# guhPLC_V0_2.net
KiCad netlist of a schematic drawn in EAGLE
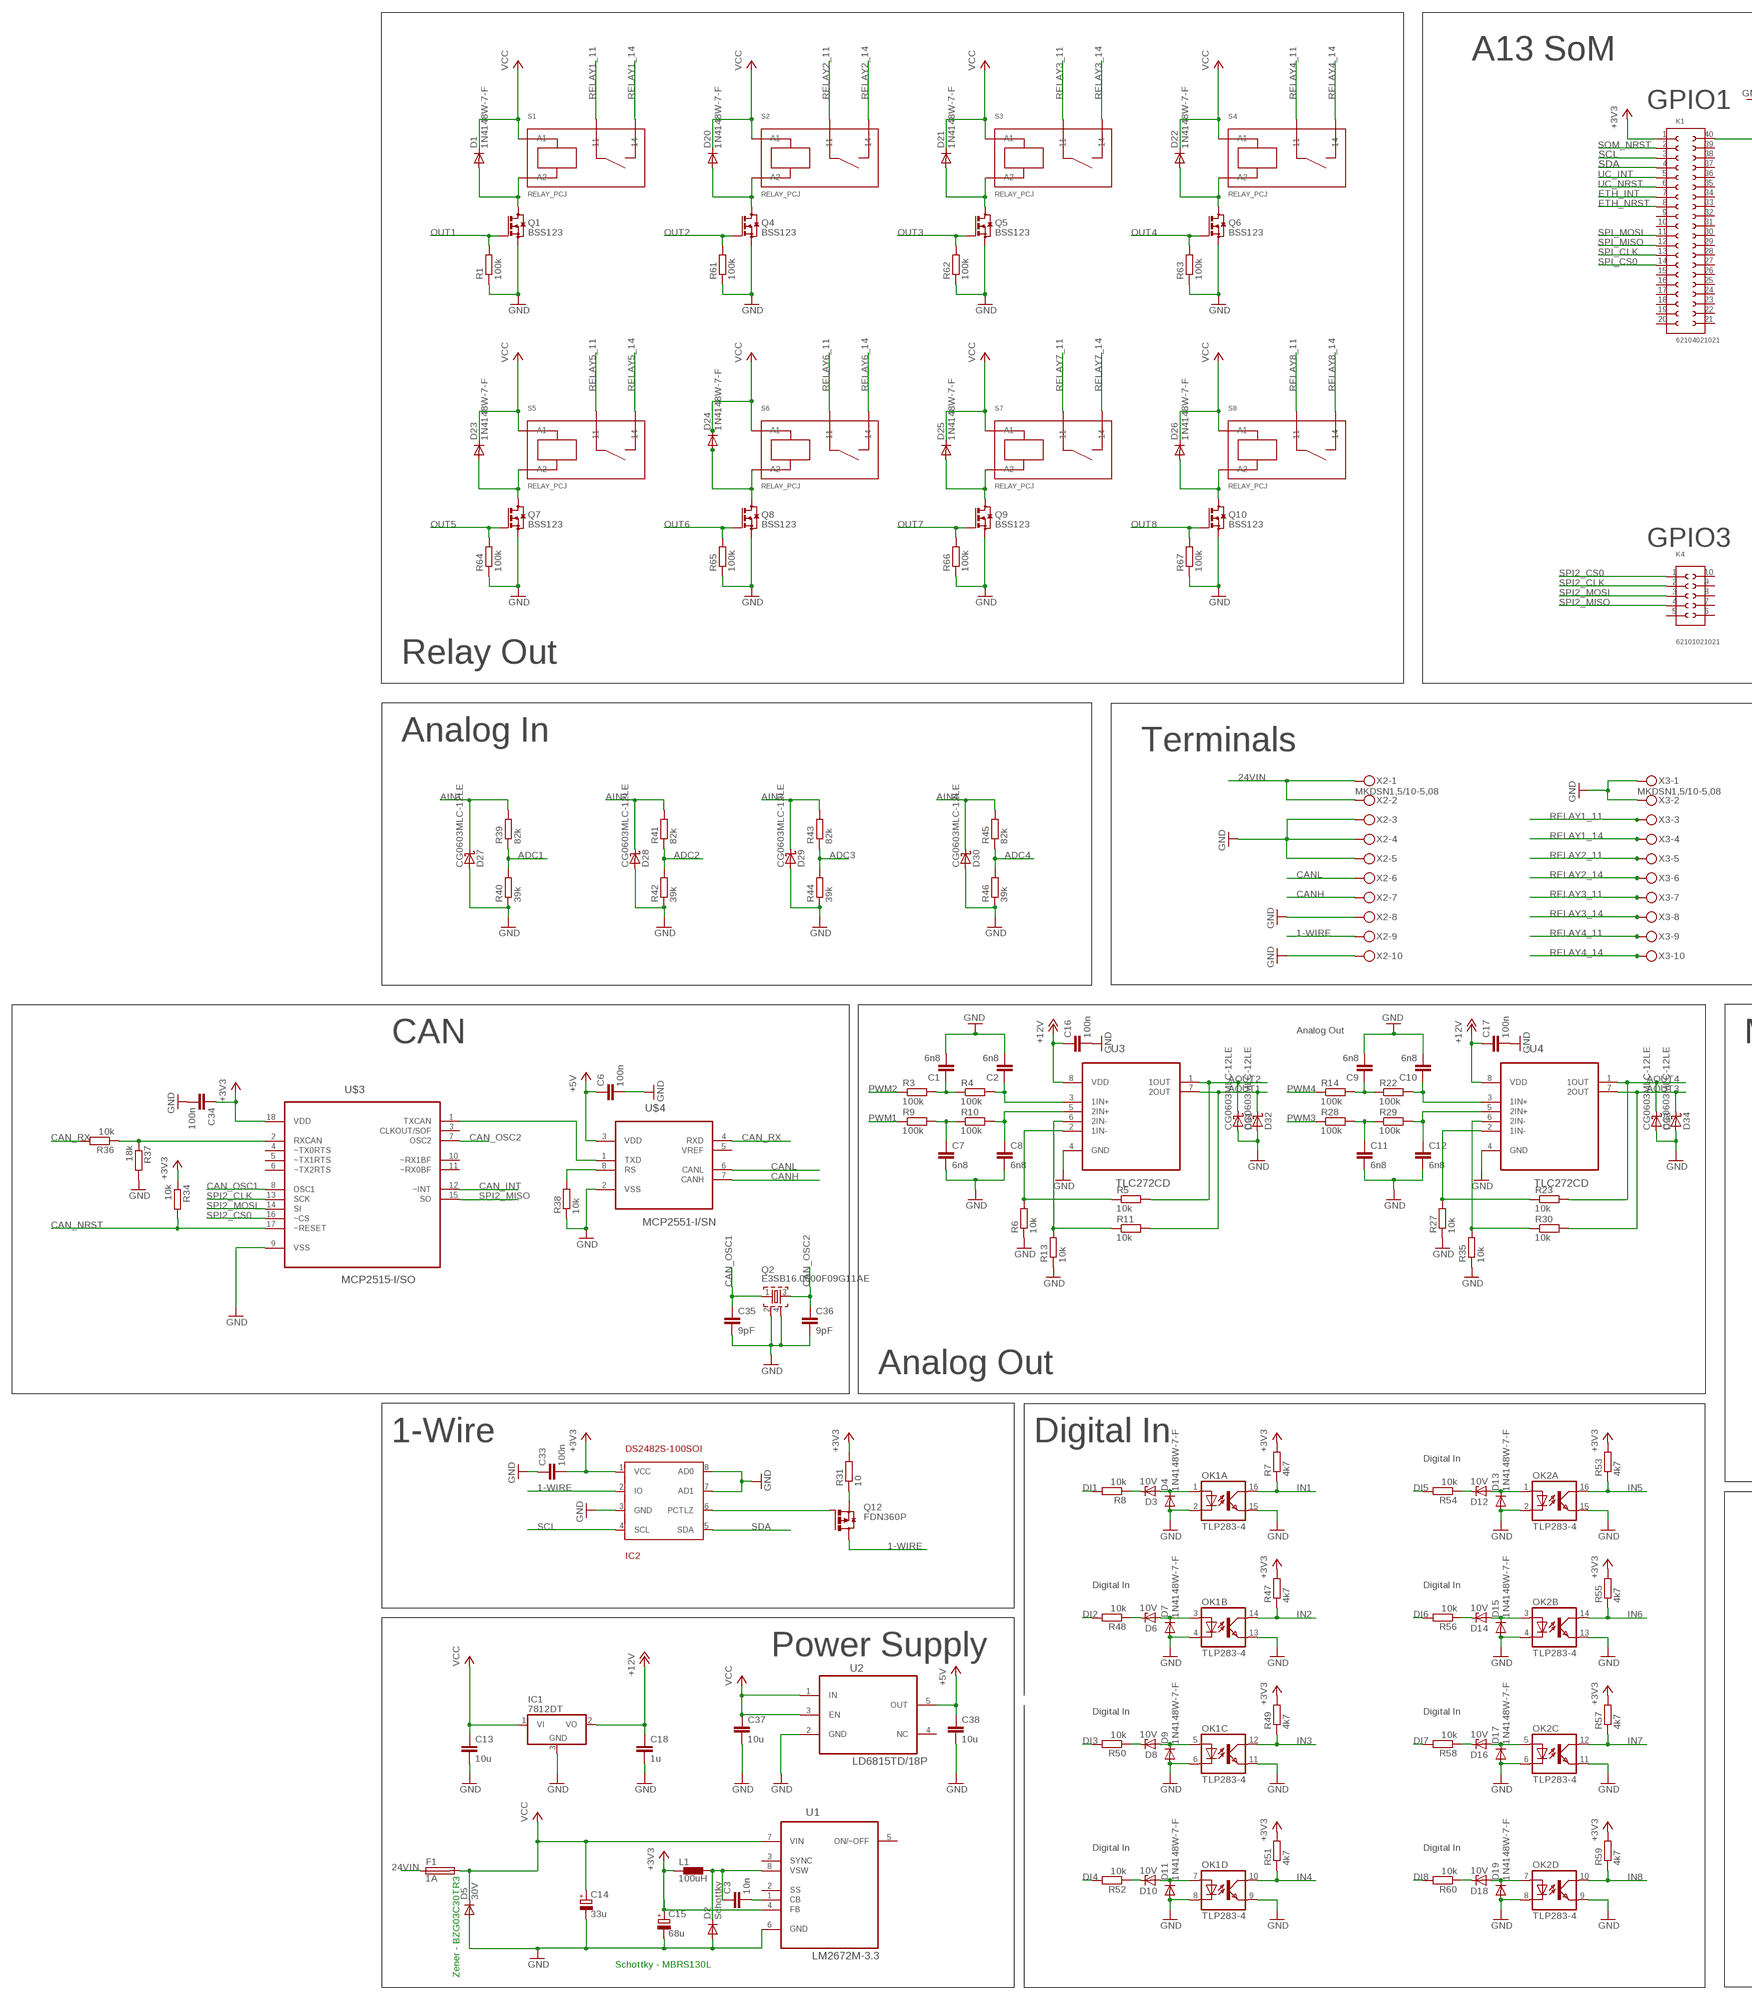
[diagram p0: schematic, sheet 1, part 1 of 2]
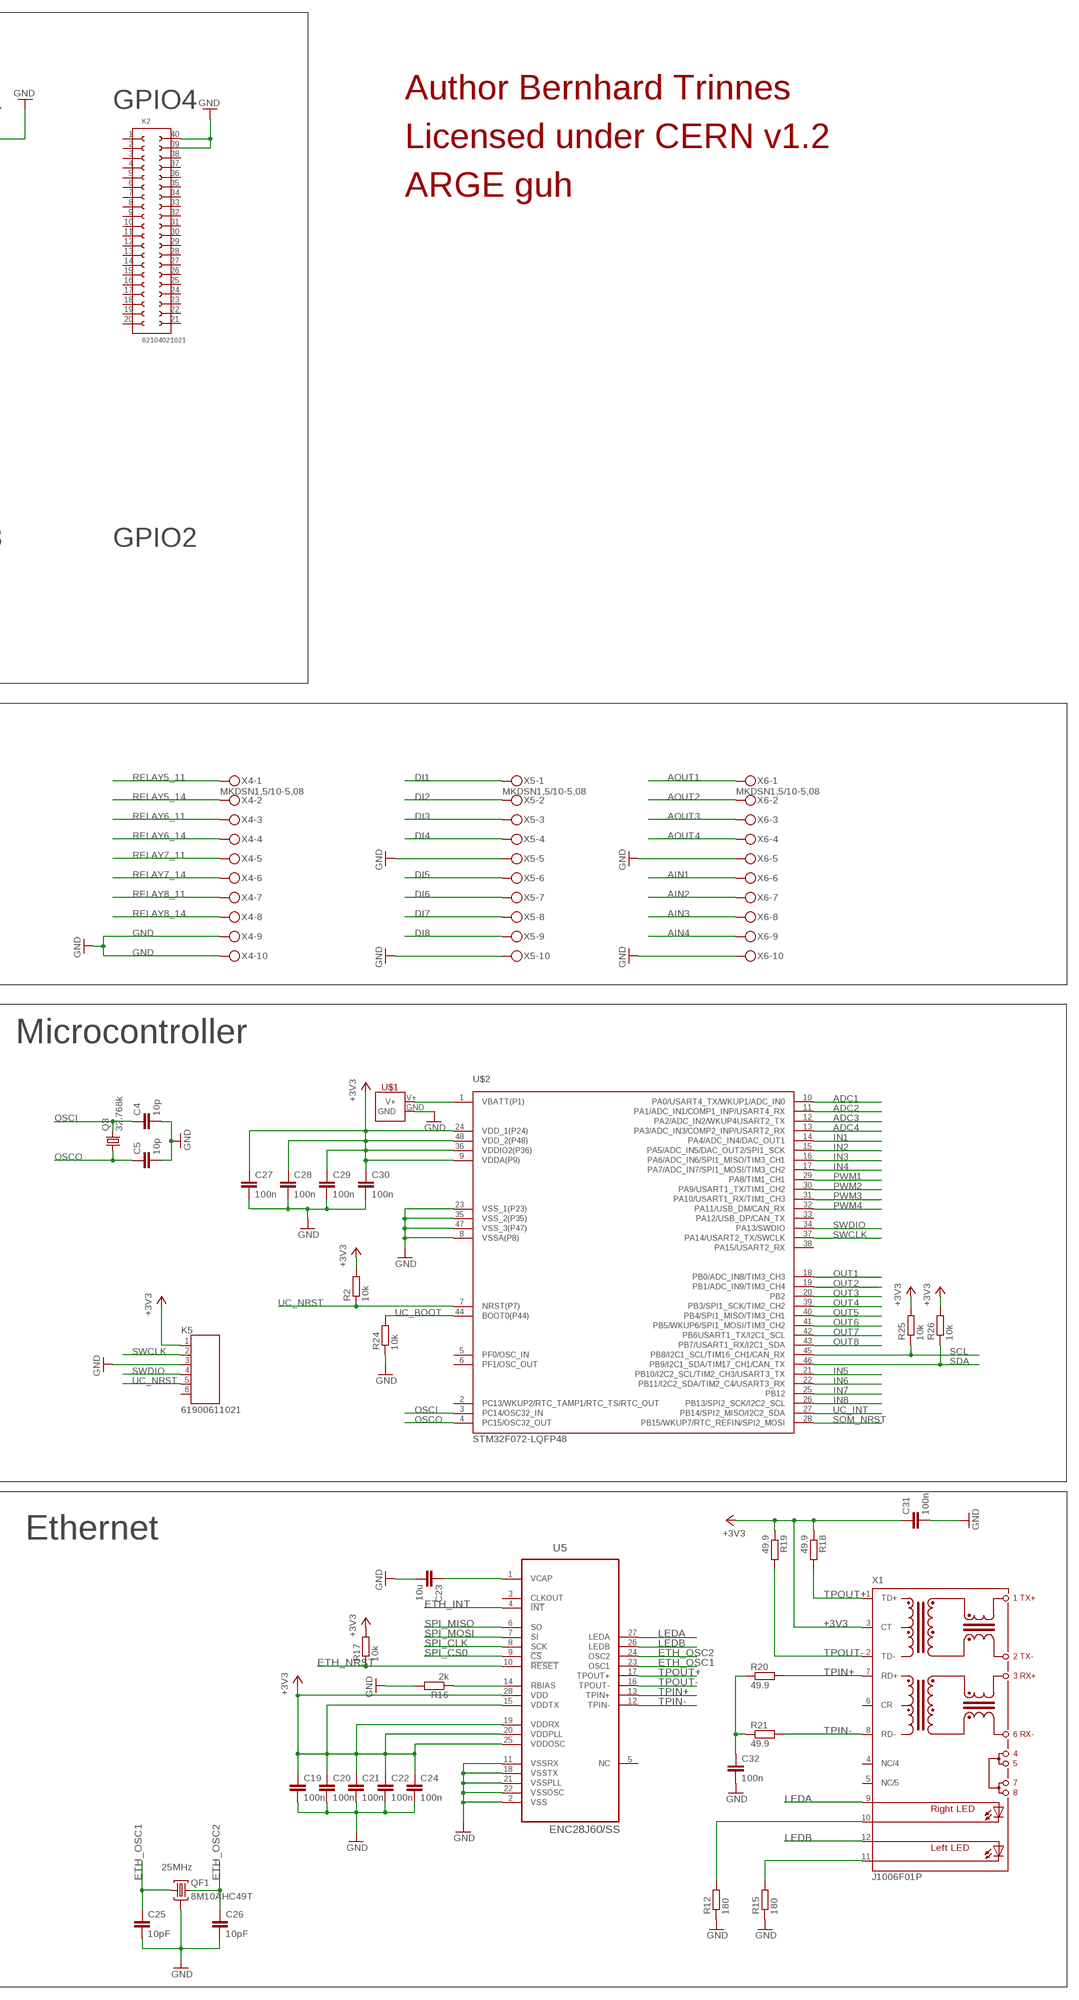
[diagram p1: schematic, sheet 1, part 2 of 2]

(export (version "E")
  (design (tool "Eeschema 10.0.6"))
  (components
    (comp (ref "C1")
      (value "6n8")
      (footprint "eagle-import:C0603")
      (libsource (lib "eagle-import") (part "C-EUC0603"))
    )
    (comp (ref "C2")
      (value "6n8")
      (footprint "eagle-import:C0603")
      (libsource (lib "eagle-import") (part "C-EUC0603"))
    )
    (comp (ref "C3")
      (value "10n")
      (footprint "eagle-import:C0603")
      (libsource (lib "eagle-import") (part "C-EUC0603"))
    )
    (comp (ref "C4")
      (value "10p")
      (footprint "eagle-import:C0603")
      (libsource (lib "eagle-import") (part "C-EUC0603"))
    )
    (comp (ref "C5")
      (value "10p")
      (footprint "eagle-import:C0603")
      (libsource (lib "eagle-import") (part "C-EUC0603"))
    )
    (comp (ref "C6")
      (value "100n")
      (footprint "eagle-import:C0603")
      (libsource (lib "eagle-import") (part "C-EUC0603"))
    )
    (comp (ref "C7")
      (value "6n8")
      (footprint "eagle-import:C0603")
      (libsource (lib "eagle-import") (part "C-EUC0603"))
    )
    (comp (ref "C8")
      (value "6n8")
      (footprint "eagle-import:C0603")
      (libsource (lib "eagle-import") (part "C-EUC0603"))
    )
    (comp (ref "C9")
      (value "6n8")
      (footprint "eagle-import:C0603")
      (libsource (lib "eagle-import") (part "C-EUC0603"))
    )
    (comp (ref "C10")
      (value "6n8")
      (footprint "eagle-import:C0603")
      (libsource (lib "eagle-import") (part "C-EUC0603"))
    )
    (comp (ref "C11")
      (value "6n8")
      (footprint "eagle-import:C0603")
      (libsource (lib "eagle-import") (part "C-EUC0603"))
    )
    (comp (ref "C12")
      (value "6n8")
      (footprint "eagle-import:C0603")
      (libsource (lib "eagle-import") (part "C-EUC0603"))
    )
    (comp (ref "C13")
      (value "10u")
      (footprint "eagle-import:C1206")
      (libsource (lib "eagle-import") (part "C-EUC1206"))
    )
    (comp (ref "C14")
      (value "33u")
      (footprint "eagle-import:CT7343")
      (libsource (lib "eagle-import") (part "CPOL-EUCT7343"))
    )
    (comp (ref "C15")
      (value "68u")
      (footprint "eagle-import:CT6032")
      (libsource (lib "eagle-import") (part "CPOL-EUCT6032"))
    )
    (comp (ref "C16")
      (value "100n")
      (footprint "eagle-import:C0603")
      (libsource (lib "eagle-import") (part "C-EUC0603"))
    )
    (comp (ref "C17")
      (value "100n")
      (footprint "eagle-import:C0603")
      (libsource (lib "eagle-import") (part "C-EUC0603"))
    )
    (comp (ref "C18")
      (value "1u")
      (footprint "eagle-import:C1206")
      (libsource (lib "eagle-import") (part "C-EUC1206"))
    )
    (comp (ref "C19")
      (value "100n")
      (footprint "eagle-import:C0603")
      (libsource (lib "eagle-import") (part "C-EUC0603"))
    )
    (comp (ref "C20")
      (value "100n")
      (footprint "eagle-import:C0603")
      (libsource (lib "eagle-import") (part "C-EUC0603"))
    )
    (comp (ref "C21")
      (value "100n")
      (footprint "eagle-import:C0603")
      (libsource (lib "eagle-import") (part "C-EUC0603"))
    )
    (comp (ref "C22")
      (value "100n")
      (footprint "eagle-import:C0603")
      (libsource (lib "eagle-import") (part "C-EUC0603"))
    )
    (comp (ref "C23")
      (value "10u")
      (footprint "eagle-import:C0603")
      (libsource (lib "eagle-import") (part "C-EUC0603"))
    )
    (comp (ref "C24")
      (value "100n")
      (footprint "eagle-import:C0603")
      (libsource (lib "eagle-import") (part "C-EUC0603"))
    )
    (comp (ref "C25")
      (value "10pF")
      (footprint "eagle-import:C0603")
      (libsource (lib "eagle-import") (part "C-EUC0603"))
    )
    (comp (ref "C26")
      (value "10pF")
      (footprint "eagle-import:C0603")
      (libsource (lib "eagle-import") (part "C-EUC0603"))
    )
    (comp (ref "C27")
      (value "100n")
      (footprint "eagle-import:C0603")
      (libsource (lib "eagle-import") (part "C-EUC0603"))
    )
    (comp (ref "C28")
      (value "100n")
      (footprint "eagle-import:C0603")
      (libsource (lib "eagle-import") (part "C-EUC0603"))
    )
    (comp (ref "C29")
      (value "100n")
      (footprint "eagle-import:C0603")
      (libsource (lib "eagle-import") (part "C-EUC0603"))
    )
    (comp (ref "C30")
      (value "100n")
      (footprint "eagle-import:C0603")
      (libsource (lib "eagle-import") (part "C-EUC0603"))
    )
    (comp (ref "C31")
      (value "100n")
      (footprint "eagle-import:C0603")
      (libsource (lib "eagle-import") (part "C-EUC0603"))
    )
    (comp (ref "C32")
      (value "100n")
      (footprint "eagle-import:C0402")
      (libsource (lib "eagle-import") (part "C-EUC0402"))
    )
    (comp (ref "C33")
      (value "100n")
      (footprint "eagle-import:C0603")
      (libsource (lib "eagle-import") (part "C-EUC0603"))
    )
    (comp (ref "C34")
      (value "100n")
      (footprint "eagle-import:C0603")
      (libsource (lib "eagle-import") (part "C-EUC0603"))
    )
    (comp (ref "C35")
      (value "9pF")
      (footprint "eagle-import:C0603")
      (libsource (lib "eagle-import") (part "C-EUC0603"))
    )
    (comp (ref "C36")
      (value "9pF")
      (footprint "eagle-import:C0603")
      (libsource (lib "eagle-import") (part "C-EUC0603"))
    )
    (comp (ref "C37")
      (value "10u")
      (footprint "eagle-import:C1206")
      (libsource (lib "eagle-import") (part "C-EUC1206"))
    )
    (comp (ref "C38")
      (value "10u")
      (footprint "eagle-import:C1206")
      (libsource (lib "eagle-import") (part "C-EUC1206"))
    )
    (comp (ref "D1")
      (value "1N4148W-7-F")
      (footprint "eagle-import:SOD123")
      (libsource (lib "eagle-import") (part "1N4148W-7-F"))
    )
    (comp (ref "D2")
      (value "Schottky")
      (footprint "eagle-import:DO214AA")
      (libsource (lib "eagle-import") (part "DIODE-DO214AA"))
    )
    (comp (ref "D3")
      (value "10V")
      (footprint "eagle-import:SOD80C")
      (libsource (lib "eagle-import") (part "ZENER-DIODESOD80C"))
    )
    (comp (ref "D4")
      (value "1N4148W-7-F")
      (footprint "eagle-import:SOD123")
      (libsource (lib "eagle-import") (part "1N4148W-7-F"))
    )
    (comp (ref "D5")
      (value "30V")
      (footprint "eagle-import:DO214AC")
      (libsource (lib "eagle-import") (part "DIODE-DO214AC"))
    )
    (comp (ref "D6")
      (value "10V")
      (footprint "eagle-import:SOD80C")
      (libsource (lib "eagle-import") (part "ZENER-DIODESOD80C"))
    )
    (comp (ref "D7")
      (value "1N4148W-7-F")
      (footprint "eagle-import:SOD123")
      (libsource (lib "eagle-import") (part "1N4148W-7-F"))
    )
    (comp (ref "D8")
      (value "10V")
      (footprint "eagle-import:SOD80C")
      (libsource (lib "eagle-import") (part "ZENER-DIODESOD80C"))
    )
    (comp (ref "D9")
      (value "1N4148W-7-F")
      (footprint "eagle-import:SOD123")
      (libsource (lib "eagle-import") (part "1N4148W-7-F"))
    )
    (comp (ref "D10")
      (value "10V")
      (footprint "eagle-import:SOD80C")
      (libsource (lib "eagle-import") (part "ZENER-DIODESOD80C"))
    )
    (comp (ref "D11")
      (value "1N4148W-7-F")
      (footprint "eagle-import:SOD123")
      (libsource (lib "eagle-import") (part "1N4148W-7-F"))
    )
    (comp (ref "D12")
      (value "10V")
      (footprint "eagle-import:SOD80C")
      (libsource (lib "eagle-import") (part "ZENER-DIODESOD80C"))
    )
    (comp (ref "D13")
      (value "1N4148W-7-F")
      (footprint "eagle-import:SOD123")
      (libsource (lib "eagle-import") (part "1N4148W-7-F"))
    )
    (comp (ref "D14")
      (value "10V")
      (footprint "eagle-import:SOD80C")
      (libsource (lib "eagle-import") (part "ZENER-DIODESOD80C"))
    )
    (comp (ref "D15")
      (value "1N4148W-7-F")
      (footprint "eagle-import:SOD123")
      (libsource (lib "eagle-import") (part "1N4148W-7-F"))
    )
    (comp (ref "D16")
      (value "10V")
      (footprint "eagle-import:SOD80C")
      (libsource (lib "eagle-import") (part "ZENER-DIODESOD80C"))
    )
    (comp (ref "D17")
      (value "1N4148W-7-F")
      (footprint "eagle-import:SOD123")
      (libsource (lib "eagle-import") (part "1N4148W-7-F"))
    )
    (comp (ref "D18")
      (value "10V")
      (footprint "eagle-import:SOD80C")
      (libsource (lib "eagle-import") (part "ZENER-DIODESOD80C"))
    )
    (comp (ref "D19")
      (value "1N4148W-7-F")
      (footprint "eagle-import:SOD123")
      (libsource (lib "eagle-import") (part "1N4148W-7-F"))
    )
    (comp (ref "D20")
      (value "1N4148W-7-F")
      (footprint "eagle-import:SOD123")
      (libsource (lib "eagle-import") (part "1N4148W-7-F"))
    )
    (comp (ref "D21")
      (value "1N4148W-7-F")
      (footprint "eagle-import:SOD123")
      (libsource (lib "eagle-import") (part "1N4148W-7-F"))
    )
    (comp (ref "D22")
      (value "1N4148W-7-F")
      (footprint "eagle-import:SOD123")
      (libsource (lib "eagle-import") (part "1N4148W-7-F"))
    )
    (comp (ref "D23")
      (value "1N4148W-7-F")
      (footprint "eagle-import:SOD123")
      (libsource (lib "eagle-import") (part "1N4148W-7-F"))
    )
    (comp (ref "D24")
      (value "1N4148W-7-F")
      (footprint "eagle-import:SOD123")
      (libsource (lib "eagle-import") (part "1N4148W-7-F"))
    )
    (comp (ref "D25")
      (value "1N4148W-7-F")
      (footprint "eagle-import:SOD123")
      (libsource (lib "eagle-import") (part "1N4148W-7-F"))
    )
    (comp (ref "D26")
      (value "1N4148W-7-F")
      (footprint "eagle-import:SOD123")
      (libsource (lib "eagle-import") (part "1N4148W-7-F"))
    )
    (comp (ref "D27")
      (value "CG0603MLC-12LE")
      (footprint "eagle-import:R0603")
      (libsource (lib "eagle-import") (part "CG0603MLC-12LE"))
    )
    (comp (ref "D28")
      (value "CG0603MLC-12LE")
      (footprint "eagle-import:R0603")
      (libsource (lib "eagle-import") (part "CG0603MLC-12LE"))
    )
    (comp (ref "D29")
      (value "CG0603MLC-12LE")
      (footprint "eagle-import:R0603")
      (libsource (lib "eagle-import") (part "CG0603MLC-12LE"))
    )
    (comp (ref "D30")
      (value "CG0603MLC-12LE")
      (footprint "eagle-import:R0603")
      (libsource (lib "eagle-import") (part "CG0603MLC-12LE"))
    )
    (comp (ref "D31")
      (value "CG0603MLC-12LE")
      (footprint "eagle-import:R0603")
      (libsource (lib "eagle-import") (part "CG0603MLC-12LE"))
    )
    (comp (ref "D32")
      (value "CG0603MLC-12LE")
      (footprint "eagle-import:R0603")
      (libsource (lib "eagle-import") (part "CG0603MLC-12LE"))
    )
    (comp (ref "D33")
      (value "CG0603MLC-12LE")
      (footprint "eagle-import:R0603")
      (libsource (lib "eagle-import") (part "CG0603MLC-12LE"))
    )
    (comp (ref "D34")
      (value "CG0603MLC-12LE")
      (footprint "eagle-import:R0603")
      (libsource (lib "eagle-import") (part "CG0603MLC-12LE"))
    )
    (comp (ref "F1")
      (value "1A")
      (footprint "eagle-import:LITTLEFUSE")
      (libsource (lib "eagle-import") (part "LITTLEFUSE"))
    )
    (comp (ref "IC1")
      (value "7812DT")
      (footprint "eagle-import:TO252")
      (libsource (lib "eagle-import") (part "78DT12"))
    )
    (comp (ref "IC2")
      (value "DS2482S-100SOI")
      (footprint "eagle-import:SOIC127P600X175-8N")
      (libsource (lib "eagle-import") (part "DS2482S-100SOI"))
    )
    (comp (ref "K1")
      (value "62104021021")
      (footprint "eagle-import:62104021021")
      (libsource (lib "eagle-import") (part "62104021021"))
    )
    (comp (ref "K2")
      (value "62104021021")
      (footprint "eagle-import:62104021021")
      (libsource (lib "eagle-import") (part "62104021021"))
    )
    (comp (ref "K4")
      (value "62101021021")
      (footprint "eagle-import:62101021021")
      (libsource (lib "eagle-import") (part "62101021021"))
    )
    (comp (ref "K5")
      (value "61900611021")
      (footprint "eagle-import:61900611021")
      (libsource (lib "eagle-import") (part "61900611021"))
    )
    (comp (ref "L1")
      (value "100uH")
      (footprint "eagle-import:DR1030")
      (libsource (lib "eagle-import") (part "DR1030"))
    )
    (comp (ref "OK1")
      (value "TLP283-4")
      (footprint "eagle-import:MINI-FLAT-16")
      (libsource (lib "eagle-import") (part "TLP283-4"))
    )
    (comp (ref "OK2")
      (value "TLP283-4")
      (footprint "eagle-import:MINI-FLAT-16")
      (libsource (lib "eagle-import") (part "TLP283-4"))
    )
    (comp (ref "Q1")
      (value "BSS123")
      (footprint "eagle-import:SOT23")
      (libsource (lib "eagle-import") (part "BSS123"))
    )
    (comp (ref "Q2")
      (value "E3SB16.0000F09G11AE")
      (footprint "eagle-import:E3SBXXXXXXXF09G11AE")
      (libsource (lib "eagle-import") (part "E3SB16.0000F09G11AE"))
    )
    (comp (ref "Q3")
      (value "32.768k")
      (footprint "eagle-import:TC26H")
      (libsource (lib "eagle-import") (part "CRYSTALTC26H"))
    )
    (comp (ref "Q4")
      (value "BSS123")
      (footprint "eagle-import:SOT23")
      (libsource (lib "eagle-import") (part "BSS123"))
    )
    (comp (ref "Q5")
      (value "BSS123")
      (footprint "eagle-import:SOT23")
      (libsource (lib "eagle-import") (part "BSS123"))
    )
    (comp (ref "Q6")
      (value "BSS123")
      (footprint "eagle-import:SOT23")
      (libsource (lib "eagle-import") (part "BSS123"))
    )
    (comp (ref "Q7")
      (value "BSS123")
      (footprint "eagle-import:SOT23")
      (libsource (lib "eagle-import") (part "BSS123"))
    )
    (comp (ref "Q8")
      (value "BSS123")
      (footprint "eagle-import:SOT23")
      (libsource (lib "eagle-import") (part "BSS123"))
    )
    (comp (ref "Q9")
      (value "BSS123")
      (footprint "eagle-import:SOT23")
      (libsource (lib "eagle-import") (part "BSS123"))
    )
    (comp (ref "Q10")
      (value "BSS123")
      (footprint "eagle-import:SOT23")
      (libsource (lib "eagle-import") (part "BSS123"))
    )
    (comp (ref "Q12")
      (value "FDN360P")
      (footprint "eagle-import:SUPER-SOT3")
      (libsource (lib "eagle-import") (part "FDN360P"))
    )
    (comp (ref "QF1")
      (value "8M10AHC49T")
      (footprint "eagle-import:HC49U")
      (libsource (lib "eagle-import") (part "8M10AHC49T"))
    )
    (comp (ref "R1")
      (value "100k")
      (footprint "eagle-import:R0603")
      (libsource (lib "eagle-import") (part "R-EU_R0603"))
    )
    (comp (ref "R2")
      (value "10k")
      (footprint "eagle-import:R0603")
      (libsource (lib "eagle-import") (part "R-EU_R0603"))
    )
    (comp (ref "R3")
      (value "100k")
      (footprint "eagle-import:R0603")
      (libsource (lib "eagle-import") (part "R-EU_R0603"))
    )
    (comp (ref "R4")
      (value "100k")
      (footprint "eagle-import:R0603")
      (libsource (lib "eagle-import") (part "R-EU_R0603"))
    )
    (comp (ref "R5")
      (value "10k")
      (footprint "eagle-import:R0805")
      (libsource (lib "eagle-import") (part "R-EU_R0805"))
    )
    (comp (ref "R6")
      (value "10k")
      (footprint "eagle-import:R0805")
      (libsource (lib "eagle-import") (part "R-EU_R0805"))
    )
    (comp (ref "R7")
      (value "4k7")
      (footprint "eagle-import:R0603")
      (libsource (lib "eagle-import") (part "R-EU_R0603"))
    )
    (comp (ref "R8")
      (value "10k")
      (footprint "eagle-import:R0805")
      (libsource (lib "eagle-import") (part "R-EU_R0805"))
    )
    (comp (ref "R9")
      (value "100k")
      (footprint "eagle-import:R0603")
      (libsource (lib "eagle-import") (part "R-EU_R0603"))
    )
    (comp (ref "R10")
      (value "100k")
      (footprint "eagle-import:R0603")
      (libsource (lib "eagle-import") (part "R-EU_R0603"))
    )
    (comp (ref "R11")
      (value "10k")
      (footprint "eagle-import:R0805")
      (libsource (lib "eagle-import") (part "R-EU_R0805"))
    )
    (comp (ref "R12")
      (value "180")
      (footprint "eagle-import:R0603")
      (libsource (lib "eagle-import") (part "R-EU_R0603"))
    )
    (comp (ref "R13")
      (value "10k")
      (footprint "eagle-import:R0805")
      (libsource (lib "eagle-import") (part "R-EU_R0805"))
    )
    (comp (ref "R14")
      (value "100k")
      (footprint "eagle-import:R0603")
      (libsource (lib "eagle-import") (part "R-EU_R0603"))
    )
    (comp (ref "R15")
      (value "180")
      (footprint "eagle-import:R0603")
      (libsource (lib "eagle-import") (part "R-EU_R0603"))
    )
    (comp (ref "R16")
      (value "2k")
      (footprint "eagle-import:R0603")
      (libsource (lib "eagle-import") (part "R-EU_R0603"))
    )
    (comp (ref "R17")
      (value "10k")
      (footprint "eagle-import:R0603")
      (libsource (lib "eagle-import") (part "R-EU_R0603"))
    )
    (comp (ref "R18")
      (value "49.9")
      (footprint "eagle-import:R0603")
      (libsource (lib "eagle-import") (part "R-EU_R0603"))
    )
    (comp (ref "R19")
      (value "49.9")
      (footprint "eagle-import:R0603")
      (libsource (lib "eagle-import") (part "R-EU_R0603"))
    )
    (comp (ref "R20")
      (value "49.9")
      (footprint "eagle-import:R0603")
      (libsource (lib "eagle-import") (part "R-EU_R0603"))
    )
    (comp (ref "R21")
      (value "49.9")
      (footprint "eagle-import:R0603")
      (libsource (lib "eagle-import") (part "R-EU_R0603"))
    )
    (comp (ref "R22")
      (value "100k")
      (footprint "eagle-import:R0603")
      (libsource (lib "eagle-import") (part "R-EU_R0603"))
    )
    (comp (ref "R23")
      (value "10k")
      (footprint "eagle-import:R0805")
      (libsource (lib "eagle-import") (part "R-EU_R0805"))
    )
    (comp (ref "R24")
      (value "10k")
      (footprint "eagle-import:R0603")
      (libsource (lib "eagle-import") (part "R-EU_R0603"))
    )
    (comp (ref "R25")
      (value "10k")
      (footprint "eagle-import:R0603")
      (libsource (lib "eagle-import") (part "R-EU_R0603"))
    )
    (comp (ref "R26")
      (value "10k")
      (footprint "eagle-import:R0603")
      (libsource (lib "eagle-import") (part "R-EU_R0603"))
    )
    (comp (ref "R27")
      (value "10k")
      (footprint "eagle-import:R0805")
      (libsource (lib "eagle-import") (part "R-EU_R0805"))
    )
    (comp (ref "R28")
      (value "100k")
      (footprint "eagle-import:R0603")
      (libsource (lib "eagle-import") (part "R-EU_R0603"))
    )
    (comp (ref "R29")
      (value "100k")
      (footprint "eagle-import:R0603")
      (libsource (lib "eagle-import") (part "R-EU_R0603"))
    )
    (comp (ref "R30")
      (value "10k")
      (footprint "eagle-import:R0805")
      (libsource (lib "eagle-import") (part "R-EU_R0805"))
    )
    (comp (ref "R31")
      (value "10")
      (footprint "eagle-import:R0805")
      (libsource (lib "eagle-import") (part "R-EU_R0805"))
    )
    (comp (ref "R34")
      (value "10k")
      (footprint "eagle-import:R0603")
      (libsource (lib "eagle-import") (part "R-EU_R0603"))
    )
    (comp (ref "R35")
      (value "10k")
      (footprint "eagle-import:R0805")
      (libsource (lib "eagle-import") (part "R-EU_R0805"))
    )
    (comp (ref "R36")
      (value "10k")
      (footprint "eagle-import:R0603")
      (libsource (lib "eagle-import") (part "R-EU_R0603"))
    )
    (comp (ref "R37")
      (value "18k")
      (footprint "eagle-import:R0603")
      (libsource (lib "eagle-import") (part "R-EU_R0603"))
    )
    (comp (ref "R38")
      (value "10k")
      (footprint "eagle-import:R0603")
      (libsource (lib "eagle-import") (part "R-EU_R0603"))
    )
    (comp (ref "R39")
      (value "82k")
      (footprint "eagle-import:R0805")
      (libsource (lib "eagle-import") (part "R-EU_R0805"))
    )
    (comp (ref "R40")
      (value "39k")
      (footprint "eagle-import:R0805")
      (libsource (lib "eagle-import") (part "R-EU_R0805"))
    )
    (comp (ref "R41")
      (value "82k")
      (footprint "eagle-import:R0805")
      (libsource (lib "eagle-import") (part "R-EU_R0805"))
    )
    (comp (ref "R42")
      (value "39k")
      (footprint "eagle-import:R0805")
      (libsource (lib "eagle-import") (part "R-EU_R0805"))
    )
    (comp (ref "R43")
      (value "82k")
      (footprint "eagle-import:R0805")
      (libsource (lib "eagle-import") (part "R-EU_R0805"))
    )
    (comp (ref "R44")
      (value "39k")
      (footprint "eagle-import:R0805")
      (libsource (lib "eagle-import") (part "R-EU_R0805"))
    )
    (comp (ref "R45")
      (value "82k")
      (footprint "eagle-import:R0805")
      (libsource (lib "eagle-import") (part "R-EU_R0805"))
    )
    (comp (ref "R46")
      (value "39k")
      (footprint "eagle-import:R0805")
      (libsource (lib "eagle-import") (part "R-EU_R0805"))
    )
    (comp (ref "R47")
      (value "4k7")
      (footprint "eagle-import:R0603")
      (libsource (lib "eagle-import") (part "R-EU_R0603"))
    )
    (comp (ref "R48")
      (value "10k")
      (footprint "eagle-import:R0805")
      (libsource (lib "eagle-import") (part "R-EU_R0805"))
    )
    (comp (ref "R49")
      (value "4k7")
      (footprint "eagle-import:R0603")
      (libsource (lib "eagle-import") (part "R-EU_R0603"))
    )
    (comp (ref "R50")
      (value "10k")
      (footprint "eagle-import:R0805")
      (libsource (lib "eagle-import") (part "R-EU_R0805"))
    )
    (comp (ref "R51")
      (value "4k7")
      (footprint "eagle-import:R0603")
      (libsource (lib "eagle-import") (part "R-EU_R0603"))
    )
    (comp (ref "R52")
      (value "10k")
      (footprint "eagle-import:R0805")
      (libsource (lib "eagle-import") (part "R-EU_R0805"))
    )
    (comp (ref "R53")
      (value "4k7")
      (footprint "eagle-import:R0603")
      (libsource (lib "eagle-import") (part "R-EU_R0603"))
    )
    (comp (ref "R54")
      (value "10k")
      (footprint "eagle-import:R0805")
      (libsource (lib "eagle-import") (part "R-EU_R0805"))
    )
    (comp (ref "R55")
      (value "4k7")
      (footprint "eagle-import:R0603")
      (libsource (lib "eagle-import") (part "R-EU_R0603"))
    )
    (comp (ref "R56")
      (value "10k")
      (footprint "eagle-import:R0805")
      (libsource (lib "eagle-import") (part "R-EU_R0805"))
    )
    (comp (ref "R57")
      (value "4k7")
      (footprint "eagle-import:R0603")
      (libsource (lib "eagle-import") (part "R-EU_R0603"))
    )
    (comp (ref "R58")
      (value "10k")
      (footprint "eagle-import:R0805")
      (libsource (lib "eagle-import") (part "R-EU_R0805"))
    )
    (comp (ref "R59")
      (value "4k7")
      (footprint "eagle-import:R0603")
      (libsource (lib "eagle-import") (part "R-EU_R0603"))
    )
    (comp (ref "R60")
      (value "10k")
      (footprint "eagle-import:R0805")
      (libsource (lib "eagle-import") (part "R-EU_R0805"))
    )
    (comp (ref "R61")
      (value "100k")
      (footprint "eagle-import:R0603")
      (libsource (lib "eagle-import") (part "R-EU_R0603"))
    )
    (comp (ref "R62")
      (value "100k")
      (footprint "eagle-import:R0603")
      (libsource (lib "eagle-import") (part "R-EU_R0603"))
    )
    (comp (ref "R63")
      (value "100k")
      (footprint "eagle-import:R0603")
      (libsource (lib "eagle-import") (part "R-EU_R0603"))
    )
    (comp (ref "R64")
      (value "100k")
      (footprint "eagle-import:R0603")
      (libsource (lib "eagle-import") (part "R-EU_R0603"))
    )
    (comp (ref "R65")
      (value "100k")
      (footprint "eagle-import:R0603")
      (libsource (lib "eagle-import") (part "R-EU_R0603"))
    )
    (comp (ref "R66")
      (value "100k")
      (footprint "eagle-import:R0603")
      (libsource (lib "eagle-import") (part "R-EU_R0603"))
    )
    (comp (ref "R67")
      (value "100k")
      (footprint "eagle-import:R0603")
      (libsource (lib "eagle-import") (part "R-EU_R0603"))
    )
    (comp (ref "S1")
      (value "RELAY_PCJ")
      (footprint "eagle-import:RELAY_PCJ")
      (libsource (lib "eagle-import") (part "RELAY_PCJ"))
    )
    (comp (ref "S2")
      (value "RELAY_PCJ")
      (footprint "eagle-import:RELAY_PCJ")
      (libsource (lib "eagle-import") (part "RELAY_PCJ"))
    )
    (comp (ref "S3")
      (value "RELAY_PCJ")
      (footprint "eagle-import:RELAY_PCJ")
      (libsource (lib "eagle-import") (part "RELAY_PCJ"))
    )
    (comp (ref "S4")
      (value "RELAY_PCJ")
      (footprint "eagle-import:RELAY_PCJ")
      (libsource (lib "eagle-import") (part "RELAY_PCJ"))
    )
    (comp (ref "S5")
      (value "RELAY_PCJ")
      (footprint "eagle-import:RELAY_PCJ")
      (libsource (lib "eagle-import") (part "RELAY_PCJ"))
    )
    (comp (ref "S6")
      (value "RELAY_PCJ")
      (footprint "eagle-import:RELAY_PCJ")
      (libsource (lib "eagle-import") (part "RELAY_PCJ"))
    )
    (comp (ref "S7")
      (value "RELAY_PCJ")
      (footprint "eagle-import:RELAY_PCJ")
      (libsource (lib "eagle-import") (part "RELAY_PCJ"))
    )
    (comp (ref "S8")
      (value "RELAY_PCJ")
      (footprint "eagle-import:RELAY_PCJ")
      (libsource (lib "eagle-import") (part "RELAY_PCJ"))
    )
    (comp (ref "U$1")
      (value "MULTICOMP-CH7410-2032LF")
      (footprint "eagle-import:MULTICOMP-CH7410-2032LF")
      (libsource (lib "eagle-import") (part "MULTICOMP-CH7410-2032LF"))
    )
    (comp (ref "U$2")
      (value "STM32F072-LQFP48")
      (footprint "eagle-import:LQFP48")
      (libsource (lib "eagle-import") (part "STM32F072-LQFP48"))
    )
    (comp (ref "U$3")
      (value "MCP2515-I/SO")
      (footprint "eagle-import:SOIC127P1034X264-18N")
      (libsource (lib "eagle-import") (part "MCP2515-I/SO"))
    )
    (comp (ref "U$4")
      (value "MCP2551-I/SN")
      (footprint "eagle-import:SOIC127P600X175-8N")
      (libsource (lib "eagle-import") (part "MCP2551-I/SN"))
    )
    (comp (ref "U1")
      (value "LM2672M-3.3")
      (footprint "eagle-import:SOIC127P600X175-8N")
      (libsource (lib "eagle-import") (part "LM2672M-3.3"))
    )
    (comp (ref "U2")
      (value "LD6815TD/18P")
      (footprint "eagle-import:SOT95P275X110-5N")
      (libsource (lib "eagle-import") (part "LD6815TD/18P"))
    )
    (comp (ref "U3")
      (value "TLC272CD")
      (footprint "eagle-import:SOIC127P600X175-8N")
      (libsource (lib "eagle-import") (part "TLC272CD"))
    )
    (comp (ref "U4")
      (value "TLC272CD")
      (footprint "eagle-import:SOIC127P600X175-8N")
      (libsource (lib "eagle-import") (part "TLC272CD"))
    )
    (comp (ref "U5")
      (value "ENC28J60/SS")
      (footprint "eagle-import:SOP65P780X200-28N")
      (libsource (lib "eagle-import") (part "ENC28J60/SS"))
    )
    (comp (ref "X1")
      (value "J1006F01P")
      (footprint "eagle-import:J1")
      (libsource (lib "eagle-import") (part "J1006F01P"))
    )
    (comp (ref "X2")
      (value "MKDSN1,5/10-5,08")
      (footprint "eagle-import:MKDSN1,5_10-5,08")
      (fields (field (name "MPN") "SMKDSN1,5/10-5,08"))
      (libsource (lib "eagle-import") (part "MKDSN1,5/10-5,08"))
    )
    (comp (ref "X3")
      (value "MKDSN1,5/10-5,08")
      (footprint "eagle-import:MKDSN1,5_10-5,08")
      (fields (field (name "MPN") "SMKDSN1,5/10-5,08"))
      (libsource (lib "eagle-import") (part "MKDSN1,5/10-5,08"))
    )
    (comp (ref "X4")
      (value "MKDSN1,5/10-5,08")
      (footprint "eagle-import:MKDSN1,5_10-5,08")
      (fields (field (name "MPN") "SMKDSN1,5/10-5,08"))
      (libsource (lib "eagle-import") (part "MKDSN1,5/10-5,08"))
    )
    (comp (ref "X5")
      (value "MKDSN1,5/10-5,08")
      (footprint "eagle-import:MKDSN1,5_10-5,08")
      (fields (field (name "MPN") "SMKDSN1,5/10-5,08"))
      (libsource (lib "eagle-import") (part "MKDSN1,5/10-5,08"))
    )
    (comp (ref "X6")
      (value "MKDSN1,5/10-5,08")
      (footprint "eagle-import:MKDSN1,5_10-5,08")
      (fields (field (name "MPN") "SMKDSN1,5/10-5,08"))
      (libsource (lib "eagle-import") (part "MKDSN1,5/10-5,08"))
    )
  )
  (nets
    (net (code "1") (name "+3V3") (class "Default")
      (node (ref "C15") (pin "+") (pinfunction "+_+") (pintype "passive"))
      (node (ref "C19") (pin "1") (pinfunction "1_1") (pintype "passive"))
      (node (ref "C20") (pin "1") (pinfunction "1_1") (pintype "passive"))
      (node (ref "C21") (pin "1") (pinfunction "1_1") (pintype "passive"))
      (node (ref "C22") (pin "1") (pinfunction "1_1") (pintype "passive"))
      (node (ref "C24") (pin "1") (pinfunction "1_1") (pintype "passive"))
      (node (ref "C27") (pin "1") (pinfunction "1_1") (pintype "passive"))
      (node (ref "C28") (pin "1") (pinfunction "1_1") (pintype "passive"))
      (node (ref "C29") (pin "1") (pinfunction "1_1") (pintype "passive"))
      (node (ref "C30") (pin "1") (pinfunction "1_1") (pintype "passive"))
      (node (ref "C31") (pin "1") (pinfunction "1_1") (pintype "passive"))
      (node (ref "C33") (pin "2") (pinfunction "2_2") (pintype "passive"))
      (node (ref "C34") (pin "1") (pinfunction "1_1") (pintype "passive"))
      (node (ref "IC2") (pin "1") (pinfunction "VCC_1") (pintype "power_in"))
      (node (ref "K1") (pin "1") (pinfunction "1_1") (pintype "passive"))
      (node (ref "K5") (pin "1") (pinfunction "1_1") (pintype "passive"))
      (node (ref "L1") (pin "1") (pinfunction "1_1") (pintype "passive"))
      (node (ref "R17") (pin "2") (pinfunction "2_2") (pintype "passive"))
      (node (ref "R18") (pin "1") (pinfunction "1_1") (pintype "passive"))
      (node (ref "R19") (pin "1") (pinfunction "1_1") (pintype "passive"))
      (node (ref "R2") (pin "2") (pinfunction "2_2") (pintype "passive"))
      (node (ref "R25") (pin "2") (pinfunction "2_2") (pintype "passive"))
      (node (ref "R26") (pin "2") (pinfunction "2_2") (pintype "passive"))
      (node (ref "R31") (pin "2") (pinfunction "2_2") (pintype "passive"))
      (node (ref "R34") (pin "1") (pinfunction "1_1") (pintype "passive"))
      (node (ref "R47") (pin "2") (pinfunction "2_2") (pintype "passive"))
      (node (ref "R49") (pin "2") (pinfunction "2_2") (pintype "passive"))
      (node (ref "R51") (pin "2") (pinfunction "2_2") (pintype "passive"))
      (node (ref "R53") (pin "2") (pinfunction "2_2") (pintype "passive"))
      (node (ref "R55") (pin "2") (pinfunction "2_2") (pintype "passive"))
      (node (ref "R57") (pin "2") (pinfunction "2_2") (pintype "passive"))
      (node (ref "R59") (pin "2") (pinfunction "2_2") (pintype "passive"))
      (node (ref "R7") (pin "2") (pinfunction "2_2") (pintype "passive"))
      (node (ref "U$2") (pin "24") (pinfunction "VDD_1(P24)_24") (pintype "bidirectional"))
      (node (ref "U$2") (pin "36") (pinfunction "VDDIO2(P36)_36") (pintype "bidirectional"))
      (node (ref "U$2") (pin "48") (pinfunction "VDD_2(P48)_48") (pintype "bidirectional"))
      (node (ref "U$2") (pin "9") (pinfunction "VDDA(P9)_9") (pintype "bidirectional"))
      (node (ref "U$3") (pin "18") (pinfunction "VDD_18") (pintype "power_in"))
      (node (ref "U1") (pin "4") (pinfunction "FB_4") (pintype "input"))
      (node (ref "U5") (pin "15") (pinfunction "VDDTX_15") (pintype "power_in"))
      (node (ref "U5") (pin "19") (pinfunction "VDDRX_19") (pintype "power_in"))
      (node (ref "U5") (pin "20") (pinfunction "VDDPLL_20") (pintype "power_in"))
      (node (ref "U5") (pin "25") (pinfunction "VDDOSC_25") (pintype "power_in"))
      (node (ref "U5") (pin "28") (pinfunction "VDD_28") (pintype "power_in"))
      (node (ref "X1") (pin "3") (pinfunction "CT_3") (pintype "input"))
    )
    (net (code "2") (name "+5V") (class "Default")
      (node (ref "C38") (pin "1") (pinfunction "1_1") (pintype "passive"))
      (node (ref "C6") (pin "1") (pinfunction "1_1") (pintype "passive"))
      (node (ref "U$4") (pin "3") (pinfunction "VDD_3") (pintype "power_in"))
      (node (ref "U2") (pin "5") (pinfunction "OUT_5") (pintype "output"))
    )
    (net (code "3") (name "+12V") (class "Default")
      (node (ref "C16") (pin "1") (pinfunction "1_1") (pintype "passive"))
      (node (ref "C17") (pin "1") (pinfunction "1_1") (pintype "passive"))
      (node (ref "C18") (pin "1") (pinfunction "1_1") (pintype "passive"))
      (node (ref "IC1") (pin "2") (pinfunction "VO_2") (pintype "passive"))
      (node (ref "U3") (pin "8") (pinfunction "VDD_8") (pintype "power_in"))
      (node (ref "U4") (pin "8") (pinfunction "VDD_8") (pintype "power_in"))
    )
    (net (code "4") (name "/1-WIRE") (class "Default")
      (node (ref "IC2") (pin "2") (pinfunction "IO_2") (pintype "bidirectional"))
      (node (ref "Q12") (pin "3") (pinfunction "D_3") (pintype "passive"))
      (node (ref "X2") (pin "9") (pinfunction "KL_9") (pintype "passive"))
    )
    (net (code "5") (name "/24VIN") (class "Default")
      (node (ref "F1") (pin "1") (pinfunction "1_1") (pintype "passive"))
      (node (ref "X2") (pin "1") (pinfunction "KL_1") (pintype "passive"))
      (node (ref "X2") (pin "2") (pinfunction "KL_2") (pintype "passive"))
    )
    (net (code "6") (name "/ADC1") (class "Default")
      (node (ref "R39") (pin "1") (pinfunction "1_1") (pintype "passive"))
      (node (ref "R40") (pin "2") (pinfunction "2_2") (pintype "passive"))
      (node (ref "U$2") (pin "10") (pinfunction "PA0/USART4_TX/WKUP1/ADC_IN0_10") (pintype "bidirectional"))
    )
    (net (code "7") (name "/ADC2") (class "Default")
      (node (ref "R41") (pin "1") (pinfunction "1_1") (pintype "passive"))
      (node (ref "R42") (pin "2") (pinfunction "2_2") (pintype "passive"))
      (node (ref "U$2") (pin "11") (pinfunction "PA1/ADC_IN1/COMP1_INP/USART4_RX_11") (pintype "bidirectional"))
    )
    (net (code "8") (name "/ADC3") (class "Default")
      (node (ref "R43") (pin "1") (pinfunction "1_1") (pintype "passive"))
      (node (ref "R44") (pin "2") (pinfunction "2_2") (pintype "passive"))
      (node (ref "U$2") (pin "12") (pinfunction "PA2/ADC_IN2/WKUP4USART2_TX_12") (pintype "bidirectional"))
    )
    (net (code "9") (name "/ADC4") (class "Default")
      (node (ref "R45") (pin "1") (pinfunction "1_1") (pintype "passive"))
      (node (ref "R46") (pin "2") (pinfunction "2_2") (pintype "passive"))
      (node (ref "U$2") (pin "13") (pinfunction "PA3/ADC_IN3/COMP2_INP/USART2_RX_13") (pintype "bidirectional"))
    )
    (net (code "10") (name "/AIN1") (class "Default")
      (node (ref "D27") (pin "2") (pinfunction "C_2") (pintype "passive"))
      (node (ref "R39") (pin "2") (pinfunction "2_2") (pintype "passive"))
      (node (ref "X6") (pin "6") (pinfunction "KL_6") (pintype "passive"))
    )
    (net (code "11") (name "/AIN2") (class "Default")
      (node (ref "D28") (pin "2") (pinfunction "C_2") (pintype "passive"))
      (node (ref "R41") (pin "2") (pinfunction "2_2") (pintype "passive"))
      (node (ref "X6") (pin "7") (pinfunction "KL_7") (pintype "passive"))
    )
    (net (code "12") (name "/AIN3") (class "Default")
      (node (ref "D29") (pin "2") (pinfunction "C_2") (pintype "passive"))
      (node (ref "R43") (pin "2") (pinfunction "2_2") (pintype "passive"))
      (node (ref "X6") (pin "8") (pinfunction "KL_8") (pintype "passive"))
    )
    (net (code "13") (name "/AIN4") (class "Default")
      (node (ref "D30") (pin "2") (pinfunction "C_2") (pintype "passive"))
      (node (ref "R45") (pin "2") (pinfunction "2_2") (pintype "passive"))
      (node (ref "X6") (pin "9") (pinfunction "KL_9") (pintype "passive"))
    )
    (net (code "14") (name "/AOUT1") (class "Default")
      (node (ref "D32") (pin "2") (pinfunction "C_2") (pintype "passive"))
      (node (ref "R11") (pin "2") (pinfunction "2_2") (pintype "passive"))
      (node (ref "U3") (pin "7") (pinfunction "2OUT_7") (pintype "output"))
      (node (ref "X6") (pin "1") (pinfunction "KL_1") (pintype "passive"))
    )
    (net (code "15") (name "/AOUT2") (class "Default")
      (node (ref "D31") (pin "2") (pinfunction "C_2") (pintype "passive"))
      (node (ref "R5") (pin "2") (pinfunction "2_2") (pintype "passive"))
      (node (ref "U3") (pin "1") (pinfunction "1OUT_1") (pintype "output"))
      (node (ref "X6") (pin "2") (pinfunction "KL_2") (pintype "passive"))
    )
    (net (code "16") (name "/AOUT3") (class "Default")
      (node (ref "D34") (pin "2") (pinfunction "C_2") (pintype "passive"))
      (node (ref "R30") (pin "2") (pinfunction "2_2") (pintype "passive"))
      (node (ref "U4") (pin "7") (pinfunction "2OUT_7") (pintype "output"))
      (node (ref "X6") (pin "3") (pinfunction "KL_3") (pintype "passive"))
    )
    (net (code "17") (name "/AOUT4") (class "Default")
      (node (ref "D33") (pin "2") (pinfunction "C_2") (pintype "passive"))
      (node (ref "R23") (pin "2") (pinfunction "2_2") (pintype "passive"))
      (node (ref "U4") (pin "1") (pinfunction "1OUT_1") (pintype "output"))
      (node (ref "X6") (pin "4") (pinfunction "KL_4") (pintype "passive"))
    )
    (net (code "18") (name "/CANH") (class "Default")
      (node (ref "U$4") (pin "7") (pinfunction "CANH_7") (pintype "bidirectional"))
      (node (ref "X2") (pin "7") (pinfunction "KL_7") (pintype "passive"))
    )
    (net (code "19") (name "/CANL") (class "Default")
      (node (ref "U$4") (pin "6") (pinfunction "CANL_6") (pintype "bidirectional"))
      (node (ref "X2") (pin "6") (pinfunction "KL_6") (pintype "passive"))
    )
    (net (code "20") (name "/CAN_INT") (class "Default")
      (node (ref "U$3") (pin "12") (pinfunction "~{INT}_12") (pintype "output"))
    )
    (net (code "21") (name "/CAN_NRST") (class "Default")
      (node (ref "R34") (pin "2") (pinfunction "2_2") (pintype "passive"))
      (node (ref "U$3") (pin "17") (pinfunction "~{RESET}_17") (pintype "input"))
    )
    (net (code "22") (name "/CAN_OSC1") (class "Default")
      (node (ref "C35") (pin "1") (pinfunction "1_1") (pintype "passive"))
      (node (ref "Q2") (pin "1") (pinfunction "1_1") (pintype "passive"))
      (node (ref "U$3") (pin "8") (pinfunction "OSC1_8") (pintype "input"))
    )
    (net (code "23") (name "/CAN_OSC2") (class "Default")
      (node (ref "C36") (pin "1") (pinfunction "1_1") (pintype "passive"))
      (node (ref "Q2") (pin "3") (pinfunction "3_3") (pintype "passive"))
      (node (ref "U$3") (pin "7") (pinfunction "OSC2_7") (pintype "output"))
    )
    (net (code "24") (name "/CAN_RX") (class "Default")
      (node (ref "R36") (pin "2") (pinfunction "2_2") (pintype "passive"))
      (node (ref "U$4") (pin "4") (pinfunction "RXD_4") (pintype "output"))
    )
    (net (code "25") (name "/DI1") (class "Default")
      (node (ref "R8") (pin "2") (pinfunction "2_2") (pintype "passive"))
      (node (ref "X5") (pin "1") (pinfunction "KL_1") (pintype "passive"))
    )
    (net (code "26") (name "/DI2") (class "Default")
      (node (ref "R48") (pin "2") (pinfunction "2_2") (pintype "passive"))
      (node (ref "X5") (pin "2") (pinfunction "KL_2") (pintype "passive"))
    )
    (net (code "27") (name "/DI3") (class "Default")
      (node (ref "R50") (pin "2") (pinfunction "2_2") (pintype "passive"))
      (node (ref "X5") (pin "3") (pinfunction "KL_3") (pintype "passive"))
    )
    (net (code "28") (name "/DI4") (class "Default")
      (node (ref "R52") (pin "2") (pinfunction "2_2") (pintype "passive"))
      (node (ref "X5") (pin "4") (pinfunction "KL_4") (pintype "passive"))
    )
    (net (code "29") (name "/DI5") (class "Default")
      (node (ref "R54") (pin "2") (pinfunction "2_2") (pintype "passive"))
      (node (ref "X5") (pin "6") (pinfunction "KL_6") (pintype "passive"))
    )
    (net (code "30") (name "/DI6") (class "Default")
      (node (ref "R56") (pin "2") (pinfunction "2_2") (pintype "passive"))
      (node (ref "X5") (pin "7") (pinfunction "KL_7") (pintype "passive"))
    )
    (net (code "31") (name "/DI7") (class "Default")
      (node (ref "R58") (pin "2") (pinfunction "2_2") (pintype "passive"))
      (node (ref "X5") (pin "8") (pinfunction "KL_8") (pintype "passive"))
    )
    (net (code "32") (name "/DI8") (class "Default")
      (node (ref "R60") (pin "2") (pinfunction "2_2") (pintype "passive"))
      (node (ref "X5") (pin "9") (pinfunction "KL_9") (pintype "passive"))
    )
    (net (code "33") (name "/ETH_INT") (class "Default")
      (node (ref "K1") (pin "7") (pinfunction "7_7") (pintype "passive"))
      (node (ref "U5") (pin "4") (pinfunction "~{INT}_4") (pintype "passive"))
    )
    (net (code "34") (name "/ETH_NRST") (class "Default")
      (node (ref "K1") (pin "8") (pinfunction "8_8") (pintype "passive"))
      (node (ref "R17") (pin "1") (pinfunction "1_1") (pintype "passive"))
      (node (ref "U5") (pin "10") (pinfunction "~{RESET}_10") (pintype "passive"))
    )
    (net (code "35") (name "/ETH_OSC1") (class "Default")
      (node (ref "C25") (pin "1") (pinfunction "1_1") (pintype "passive"))
      (node (ref "QF1") (pin "1") (pinfunction "1_1") (pintype "passive"))
      (node (ref "U5") (pin "23") (pinfunction "OSC1_23") (pintype "passive"))
    )
    (net (code "36") (name "/ETH_OSC2") (class "Default")
      (node (ref "C26") (pin "1") (pinfunction "1_1") (pintype "passive"))
      (node (ref "QF1") (pin "3") (pinfunction "3_3") (pintype "passive"))
      (node (ref "U5") (pin "24") (pinfunction "OSC2_24") (pintype "passive"))
    )
    (net (code "37") (name "/IN1") (class "Default")
      (node (ref "OK1") (pin "16") (pinfunction "COL_16") (pintype "passive"))
      (node (ref "R7") (pin "1") (pinfunction "1_1") (pintype "passive"))
      (node (ref "U$2") (pin "14") (pinfunction "PA4/ADC_IN4/DAC_OUT1_14") (pintype "bidirectional"))
    )
    (net (code "38") (name "/IN2") (class "Default")
      (node (ref "OK1") (pin "14") (pinfunction "COL_14") (pintype "passive"))
      (node (ref "R47") (pin "1") (pinfunction "1_1") (pintype "passive"))
      (node (ref "U$2") (pin "15") (pinfunction "PA5/ADC_IN5/DAC_OUT2/SPI1_SCK_15") (pintype "bidirectional"))
    )
    (net (code "39") (name "/IN3") (class "Default")
      (node (ref "OK1") (pin "12") (pinfunction "COL_12") (pintype "passive"))
      (node (ref "R49") (pin "1") (pinfunction "1_1") (pintype "passive"))
      (node (ref "U$2") (pin "16") (pinfunction "PA6/ADC_IN6/SPI1_MISO/TIM3_CH1_16") (pintype "bidirectional"))
    )
    (net (code "40") (name "/IN4") (class "Default")
      (node (ref "OK1") (pin "10") (pinfunction "COL_10") (pintype "passive"))
      (node (ref "R51") (pin "1") (pinfunction "1_1") (pintype "passive"))
      (node (ref "U$2") (pin "17") (pinfunction "PA7/ADC_IN7/SPI1_MOSI/TIM3_CH2_17") (pintype "bidirectional"))
    )
    (net (code "41") (name "/IN5") (class "Default")
      (node (ref "OK2") (pin "16") (pinfunction "COL_16") (pintype "passive"))
      (node (ref "R53") (pin "1") (pinfunction "1_1") (pintype "passive"))
      (node (ref "U$2") (pin "21") (pinfunction "PB10/I2C2_SCL/TIM2_CH3/USART3_TX_21") (pintype "bidirectional"))
    )
    (net (code "42") (name "/IN6") (class "Default")
      (node (ref "OK2") (pin "14") (pinfunction "COL_14") (pintype "passive"))
      (node (ref "R55") (pin "1") (pinfunction "1_1") (pintype "passive"))
      (node (ref "U$2") (pin "22") (pinfunction "PB11/I2C2_SDA/TIM2_C4/USART3_RX_22") (pintype "bidirectional"))
    )
    (net (code "43") (name "/IN7") (class "Default")
      (node (ref "OK2") (pin "12") (pinfunction "COL_12") (pintype "passive"))
      (node (ref "R57") (pin "1") (pinfunction "1_1") (pintype "passive"))
      (node (ref "U$2") (pin "25") (pinfunction "PB12_25") (pintype "bidirectional"))
    )
    (net (code "44") (name "/IN8") (class "Default")
      (node (ref "OK2") (pin "10") (pinfunction "COL_10") (pintype "passive"))
      (node (ref "R59") (pin "1") (pinfunction "1_1") (pintype "passive"))
      (node (ref "U$2") (pin "26") (pinfunction "PB13/SPI2_SCK/I2C2_SCL_26") (pintype "bidirectional"))
    )
    (net (code "45") (name "/LEDA") (class "Default")
      (node (ref "U5") (pin "27") (pinfunction "LEDA_27") (pintype "passive"))
      (node (ref "X1") (pin "9") (pinfunction "A-R_9") (pintype "passive"))
    )
    (net (code "46") (name "/LEDB") (class "Default")
      (node (ref "U5") (pin "26") (pinfunction "LEDB_26") (pintype "passive"))
      (node (ref "X1") (pin "12") (pinfunction "A-L_12") (pintype "passive"))
    )
    (net (code "47") (name "/OSCI") (class "Default")
      (node (ref "C4") (pin "1") (pinfunction "1_1") (pintype "passive"))
      (node (ref "Q3") (pin "2") (pinfunction "2_2") (pintype "passive"))
      (node (ref "U$2") (pin "3") (pinfunction "PC14/OSC32_IN_3") (pintype "bidirectional"))
    )
    (net (code "48") (name "/OSCO") (class "Default")
      (node (ref "C5") (pin "1") (pinfunction "1_1") (pintype "passive"))
      (node (ref "Q3") (pin "1") (pinfunction "1_1") (pintype "passive"))
      (node (ref "U$2") (pin "4") (pinfunction "PC15/OSC32_OUT_4") (pintype "bidirectional"))
    )
    (net (code "49") (name "/OUT1") (class "Default")
      (node (ref "Q1") (pin "1") (pinfunction "G_1") (pintype "passive"))
      (node (ref "R1") (pin "2") (pinfunction "2_2") (pintype "passive"))
      (node (ref "U$2") (pin "18") (pinfunction "PB0/ADC_IN8/TIM3_CH3_18") (pintype "bidirectional"))
    )
    (net (code "50") (name "/OUT2") (class "Default")
      (node (ref "Q4") (pin "1") (pinfunction "G_1") (pintype "passive"))
      (node (ref "R61") (pin "2") (pinfunction "2_2") (pintype "passive"))
      (node (ref "U$2") (pin "19") (pinfunction "PB1/ADC_IN9/TIM3_CH4_19") (pintype "bidirectional"))
    )
    (net (code "51") (name "/OUT3") (class "Default")
      (node (ref "Q5") (pin "1") (pinfunction "G_1") (pintype "passive"))
      (node (ref "R62") (pin "2") (pinfunction "2_2") (pintype "passive"))
      (node (ref "U$2") (pin "20") (pinfunction "PB2_20") (pintype "bidirectional"))
    )
    (net (code "52") (name "/OUT4") (class "Default")
      (node (ref "Q6") (pin "1") (pinfunction "G_1") (pintype "passive"))
      (node (ref "R63") (pin "2") (pinfunction "2_2") (pintype "passive"))
      (node (ref "U$2") (pin "39") (pinfunction "PB3/SPI1_SCK/TIM2_CH2_39") (pintype "bidirectional"))
    )
    (net (code "53") (name "/OUT5") (class "Default")
      (node (ref "Q7") (pin "1") (pinfunction "G_1") (pintype "passive"))
      (node (ref "R64") (pin "2") (pinfunction "2_2") (pintype "passive"))
      (node (ref "U$2") (pin "40") (pinfunction "PB4/SPI1_MISO/TIM3_CH1_40") (pintype "bidirectional"))
    )
    (net (code "54") (name "/OUT6") (class "Default")
      (node (ref "Q8") (pin "1") (pinfunction "G_1") (pintype "passive"))
      (node (ref "R65") (pin "2") (pinfunction "2_2") (pintype "passive"))
      (node (ref "U$2") (pin "41") (pinfunction "PB5/WKUP6/SPI1_MOSI/TIM3_CH2_41") (pintype "bidirectional"))
    )
    (net (code "55") (name "/OUT7") (class "Default")
      (node (ref "Q9") (pin "1") (pinfunction "G_1") (pintype "passive"))
      (node (ref "R66") (pin "2") (pinfunction "2_2") (pintype "passive"))
      (node (ref "U$2") (pin "42") (pinfunction "PB6USART1_TX/I2C1_SCL_42") (pintype "bidirectional"))
    )
    (net (code "56") (name "/OUT8") (class "Default")
      (node (ref "Q10") (pin "1") (pinfunction "G_1") (pintype "passive"))
      (node (ref "R67") (pin "2") (pinfunction "2_2") (pintype "passive"))
      (node (ref "U$2") (pin "43") (pinfunction "PB7/USART1_RX/I2C1_SDA_43") (pintype "bidirectional"))
    )
    (net (code "57") (name "/PWM1") (class "Default")
      (node (ref "R9") (pin "1") (pinfunction "1_1") (pintype "passive"))
      (node (ref "U$2") (pin "29") (pinfunction "PA8/TIM1_CH1_29") (pintype "bidirectional"))
    )
    (net (code "58") (name "/PWM2") (class "Default")
      (node (ref "R3") (pin "1") (pinfunction "1_1") (pintype "passive"))
      (node (ref "U$2") (pin "30") (pinfunction "PA9/USART1_TX/TIM1_CH2_30") (pintype "bidirectional"))
    )
    (net (code "59") (name "/PWM3") (class "Default")
      (node (ref "R28") (pin "1") (pinfunction "1_1") (pintype "passive"))
      (node (ref "U$2") (pin "31") (pinfunction "PA10/USART1_RX/TIM1_CH3_31") (pintype "bidirectional"))
    )
    (net (code "60") (name "/PWM4") (class "Default")
      (node (ref "R14") (pin "1") (pinfunction "1_1") (pintype "passive"))
      (node (ref "U$2") (pin "32") (pinfunction "PA11/USB_DM/CAN_RX_32") (pintype "bidirectional"))
    )
    (net (code "61") (name "/RELAY1_11") (class "Default")
      (node (ref "S1") (pin "11") (pinfunction "11_11") (pintype "bidirectional"))
      (node (ref "X3") (pin "3") (pinfunction "KL_3") (pintype "passive"))
    )
    (net (code "62") (name "/RELAY1_14") (class "Default")
      (node (ref "S1") (pin "14") (pinfunction "14_14") (pintype "bidirectional"))
      (node (ref "X3") (pin "4") (pinfunction "KL_4") (pintype "passive"))
    )
    (net (code "63") (name "/RELAY2_11") (class "Default")
      (node (ref "S2") (pin "11") (pinfunction "11_11") (pintype "bidirectional"))
      (node (ref "X3") (pin "5") (pinfunction "KL_5") (pintype "passive"))
    )
    (net (code "64") (name "/RELAY2_14") (class "Default")
      (node (ref "S2") (pin "14") (pinfunction "14_14") (pintype "bidirectional"))
      (node (ref "X3") (pin "6") (pinfunction "KL_6") (pintype "passive"))
    )
    (net (code "65") (name "/RELAY3_11") (class "Default")
      (node (ref "S3") (pin "11") (pinfunction "11_11") (pintype "bidirectional"))
      (node (ref "X3") (pin "7") (pinfunction "KL_7") (pintype "passive"))
    )
    (net (code "66") (name "/RELAY3_14") (class "Default")
      (node (ref "S3") (pin "14") (pinfunction "14_14") (pintype "bidirectional"))
      (node (ref "X3") (pin "8") (pinfunction "KL_8") (pintype "passive"))
    )
    (net (code "67") (name "/RELAY4_11") (class "Default")
      (node (ref "S4") (pin "11") (pinfunction "11_11") (pintype "bidirectional"))
      (node (ref "X3") (pin "9") (pinfunction "KL_9") (pintype "passive"))
    )
    (net (code "68") (name "/RELAY4_14") (class "Default")
      (node (ref "S4") (pin "14") (pinfunction "14_14") (pintype "bidirectional"))
      (node (ref "X3") (pin "10") (pinfunction "KL_10") (pintype "passive"))
    )
    (net (code "69") (name "/RELAY5_11") (class "Default")
      (node (ref "S5") (pin "11") (pinfunction "11_11") (pintype "bidirectional"))
      (node (ref "X4") (pin "1") (pinfunction "KL_1") (pintype "passive"))
    )
    (net (code "70") (name "/RELAY5_14") (class "Default")
      (node (ref "S5") (pin "14") (pinfunction "14_14") (pintype "bidirectional"))
      (node (ref "X4") (pin "2") (pinfunction "KL_2") (pintype "passive"))
    )
    (net (code "71") (name "/RELAY6_11") (class "Default")
      (node (ref "S6") (pin "11") (pinfunction "11_11") (pintype "bidirectional"))
      (node (ref "X4") (pin "3") (pinfunction "KL_3") (pintype "passive"))
    )
    (net (code "72") (name "/RELAY6_14") (class "Default")
      (node (ref "S6") (pin "14") (pinfunction "14_14") (pintype "bidirectional"))
      (node (ref "X4") (pin "4") (pinfunction "KL_4") (pintype "passive"))
    )
    (net (code "73") (name "/RELAY7_11") (class "Default")
      (node (ref "S7") (pin "11") (pinfunction "11_11") (pintype "bidirectional"))
      (node (ref "X4") (pin "5") (pinfunction "KL_5") (pintype "passive"))
    )
    (net (code "74") (name "/RELAY7_14") (class "Default")
      (node (ref "S7") (pin "14") (pinfunction "14_14") (pintype "bidirectional"))
      (node (ref "X4") (pin "6") (pinfunction "KL_6") (pintype "passive"))
    )
    (net (code "75") (name "/RELAY8_11") (class "Default")
      (node (ref "S8") (pin "11") (pinfunction "11_11") (pintype "bidirectional"))
      (node (ref "X4") (pin "7") (pinfunction "KL_7") (pintype "passive"))
    )
    (net (code "76") (name "/RELAY8_14") (class "Default")
      (node (ref "S8") (pin "14") (pinfunction "14_14") (pintype "bidirectional"))
      (node (ref "X4") (pin "8") (pinfunction "KL_8") (pintype "passive"))
    )
    (net (code "77") (name "/SCL") (class "Default")
      (node (ref "IC2") (pin "4") (pinfunction "SCL_4") (pintype "bidirectional"))
      (node (ref "K1") (pin "3") (pinfunction "3_3") (pintype "passive"))
      (node (ref "R25") (pin "1") (pinfunction "1_1") (pintype "passive"))
      (node (ref "U$2") (pin "45") (pinfunction "PB8/I2C1_SCL/TIM16_CH1/CAN_RX_45") (pintype "bidirectional"))
    )
    (net (code "78") (name "/SDA") (class "Default")
      (node (ref "IC2") (pin "5") (pinfunction "SDA_5") (pintype "bidirectional"))
      (node (ref "K1") (pin "4") (pinfunction "4_4") (pintype "passive"))
      (node (ref "R26") (pin "1") (pinfunction "1_1") (pintype "passive"))
      (node (ref "U$2") (pin "46") (pinfunction "PB9/I2C1_SDA/TIM17_CH1/CAN_TX_46") (pintype "bidirectional"))
    )
    (net (code "79") (name "/SOM_NRST") (class "Default")
      (node (ref "K1") (pin "2") (pinfunction "2_2") (pintype "passive"))
      (node (ref "U$2") (pin "28") (pinfunction "PB15/WKUP7/RTC_REFIN/SPI2_MOSI_28") (pintype "bidirectional"))
    )
    (net (code "80") (name "/SPI2_CLK") (class "Default")
      (node (ref "K4") (pin "2") (pinfunction "2_2") (pintype "passive"))
      (node (ref "U$3") (pin "13") (pinfunction "SCK_13") (pintype "input"))
    )
    (net (code "81") (name "/SPI2_CS0") (class "Default")
      (node (ref "K4") (pin "1") (pinfunction "1_1") (pintype "passive"))
      (node (ref "U$3") (pin "16") (pinfunction "~{CS}_16") (pintype "input"))
    )
    (net (code "82") (name "/SPI2_MISO") (class "Default")
      (node (ref "K4") (pin "4") (pinfunction "4_4") (pintype "passive"))
      (node (ref "U$3") (pin "15") (pinfunction "SO_15") (pintype "output"))
    )
    (net (code "83") (name "/SPI2_MOSI") (class "Default")
      (node (ref "K4") (pin "3") (pinfunction "3_3") (pintype "passive"))
      (node (ref "U$3") (pin "14") (pinfunction "SI_14") (pintype "input"))
    )
    (net (code "84") (name "/SPI_CLK") (class "Default")
      (node (ref "K1") (pin "13") (pinfunction "13_13") (pintype "passive"))
      (node (ref "U5") (pin "8") (pinfunction "SCK_8") (pintype "passive"))
    )
    (net (code "85") (name "/SPI_CS0") (class "Default")
      (node (ref "K1") (pin "14") (pinfunction "14_14") (pintype "passive"))
      (node (ref "U5") (pin "9") (pinfunction "~{CS}_9") (pintype "passive"))
    )
    (net (code "86") (name "/SPI_MISO") (class "Default")
      (node (ref "K1") (pin "12") (pinfunction "12_12") (pintype "passive"))
      (node (ref "U5") (pin "6") (pinfunction "SO_6") (pintype "passive"))
    )
    (net (code "87") (name "/SPI_MOSI") (class "Default")
      (node (ref "K1") (pin "11") (pinfunction "11_11") (pintype "passive"))
      (node (ref "U5") (pin "7") (pinfunction "SI_7") (pintype "passive"))
    )
    (net (code "88") (name "/SWCLK") (class "Default")
      (node (ref "K5") (pin "2") (pinfunction "2_2") (pintype "passive"))
      (node (ref "U$2") (pin "37") (pinfunction "PA14/USART2_TX/SWCLK_37") (pintype "bidirectional"))
    )
    (net (code "89") (name "/SWDIO") (class "Default")
      (node (ref "K5") (pin "4") (pinfunction "4_4") (pintype "passive"))
      (node (ref "U$2") (pin "34") (pinfunction "PA13/SWDIO_34") (pintype "bidirectional"))
    )
    (net (code "90") (name "/TPIN+") (class "Default")
      (node (ref "R20") (pin "2") (pinfunction "2_2") (pintype "passive"))
      (node (ref "U5") (pin "13") (pinfunction "TPIN+_13") (pintype "passive"))
      (node (ref "X1") (pin "7") (pinfunction "RD+_7") (pintype "input"))
    )
    (net (code "91") (name "/TPIN-") (class "Default")
      (node (ref "R21") (pin "2") (pinfunction "2_2") (pintype "passive"))
      (node (ref "U5") (pin "12") (pinfunction "TPIN-_12") (pintype "passive"))
      (node (ref "X1") (pin "8") (pinfunction "RD-_8") (pintype "input"))
    )
    (net (code "92") (name "/TPOUT+") (class "Default")
      (node (ref "R18") (pin "2") (pinfunction "2_2") (pintype "passive"))
      (node (ref "U5") (pin "17") (pinfunction "TPOUT+_17") (pintype "passive"))
      (node (ref "X1") (pin "1") (pinfunction "TD+_1") (pintype "input"))
    )
    (net (code "93") (name "/TPOUT-") (class "Default")
      (node (ref "R19") (pin "2") (pinfunction "2_2") (pintype "passive"))
      (node (ref "U5") (pin "16") (pinfunction "TPOUT-_16") (pintype "passive"))
      (node (ref "X1") (pin "2") (pinfunction "TD-_2") (pintype "input"))
    )
    (net (code "94") (name "/UC_BOOT") (class "Default")
      (node (ref "R24") (pin "2") (pinfunction "2_2") (pintype "passive"))
      (node (ref "U$2") (pin "44") (pinfunction "BOOT0(P44)_44") (pintype "bidirectional"))
    )
    (net (code "95") (name "/UC_INT") (class "Default")
      (node (ref "K1") (pin "5") (pinfunction "5_5") (pintype "passive"))
      (node (ref "U$2") (pin "27") (pinfunction "PB14/SPI2_MISO/I2C2_SDA_27") (pintype "bidirectional"))
    )
    (net (code "96") (name "/UC_NRST") (class "Default")
      (node (ref "K1") (pin "6") (pinfunction "6_6") (pintype "passive"))
      (node (ref "K5") (pin "5") (pinfunction "5_5") (pintype "passive"))
      (node (ref "R2") (pin "1") (pinfunction "1_1") (pintype "passive"))
      (node (ref "U$2") (pin "7") (pinfunction "NRST(P7)_7") (pintype "bidirectional"))
    )
    (net (code "97") (name "GND") (class "Default")
      (node (ref "C1") (pin "2") (pinfunction "2_2") (pintype "passive"))
      (node (ref "C10") (pin "2") (pinfunction "2_2") (pintype "passive"))
      (node (ref "C11") (pin "2") (pinfunction "2_2") (pintype "passive"))
      (node (ref "C12") (pin "2") (pinfunction "2_2") (pintype "passive"))
      (node (ref "C13") (pin "2") (pinfunction "2_2") (pintype "passive"))
      (node (ref "C14") (pin "-") (pinfunction "-_-") (pintype "passive"))
      (node (ref "C15") (pin "-") (pinfunction "-_-") (pintype "passive"))
      (node (ref "C16") (pin "2") (pinfunction "2_2") (pintype "passive"))
      (node (ref "C17") (pin "2") (pinfunction "2_2") (pintype "passive"))
      (node (ref "C18") (pin "2") (pinfunction "2_2") (pintype "passive"))
      (node (ref "C19") (pin "2") (pinfunction "2_2") (pintype "passive"))
      (node (ref "C2") (pin "2") (pinfunction "2_2") (pintype "passive"))
      (node (ref "C20") (pin "2") (pinfunction "2_2") (pintype "passive"))
      (node (ref "C21") (pin "2") (pinfunction "2_2") (pintype "passive"))
      (node (ref "C22") (pin "2") (pinfunction "2_2") (pintype "passive"))
      (node (ref "C23") (pin "2") (pinfunction "2_2") (pintype "passive"))
      (node (ref "C24") (pin "2") (pinfunction "2_2") (pintype "passive"))
      (node (ref "C25") (pin "2") (pinfunction "2_2") (pintype "passive"))
      (node (ref "C26") (pin "2") (pinfunction "2_2") (pintype "passive"))
      (node (ref "C27") (pin "2") (pinfunction "2_2") (pintype "passive"))
      (node (ref "C28") (pin "2") (pinfunction "2_2") (pintype "passive"))
      (node (ref "C29") (pin "2") (pinfunction "2_2") (pintype "passive"))
      (node (ref "C30") (pin "2") (pinfunction "2_2") (pintype "passive"))
      (node (ref "C31") (pin "2") (pinfunction "2_2") (pintype "passive"))
      (node (ref "C32") (pin "2") (pinfunction "2_2") (pintype "passive"))
      (node (ref "C33") (pin "1") (pinfunction "1_1") (pintype "passive"))
      (node (ref "C34") (pin "2") (pinfunction "2_2") (pintype "passive"))
      (node (ref "C35") (pin "2") (pinfunction "2_2") (pintype "passive"))
      (node (ref "C36") (pin "2") (pinfunction "2_2") (pintype "passive"))
      (node (ref "C37") (pin "2") (pinfunction "2_2") (pintype "passive"))
      (node (ref "C38") (pin "2") (pinfunction "2_2") (pintype "passive"))
      (node (ref "C4") (pin "2") (pinfunction "2_2") (pintype "passive"))
      (node (ref "C5") (pin "2") (pinfunction "2_2") (pintype "passive"))
      (node (ref "C6") (pin "2") (pinfunction "2_2") (pintype "passive"))
      (node (ref "C7") (pin "2") (pinfunction "2_2") (pintype "passive"))
      (node (ref "C8") (pin "2") (pinfunction "2_2") (pintype "passive"))
      (node (ref "C9") (pin "2") (pinfunction "2_2") (pintype "passive"))
      (node (ref "D11") (pin "A") (pinfunction "A_A") (pintype "passive"))
      (node (ref "D13") (pin "A") (pinfunction "A_A") (pintype "passive"))
      (node (ref "D15") (pin "A") (pinfunction "A_A") (pintype "passive"))
      (node (ref "D17") (pin "A") (pinfunction "A_A") (pintype "passive"))
      (node (ref "D19") (pin "A") (pinfunction "A_A") (pintype "passive"))
      (node (ref "D2") (pin "A") (pinfunction "A_A") (pintype "passive"))
      (node (ref "D27") (pin "1") (pinfunction "A_1") (pintype "passive"))
      (node (ref "D28") (pin "1") (pinfunction "A_1") (pintype "passive"))
      (node (ref "D29") (pin "1") (pinfunction "A_1") (pintype "passive"))
      (node (ref "D30") (pin "1") (pinfunction "A_1") (pintype "passive"))
      (node (ref "D31") (pin "1") (pinfunction "A_1") (pintype "passive"))
      (node (ref "D32") (pin "1") (pinfunction "A_1") (pintype "passive"))
      (node (ref "D33") (pin "1") (pinfunction "A_1") (pintype "passive"))
      (node (ref "D34") (pin "1") (pinfunction "A_1") (pintype "passive"))
      (node (ref "D4") (pin "A") (pinfunction "A_A") (pintype "passive"))
      (node (ref "D5") (pin "A") (pinfunction "A_A") (pintype "passive"))
      (node (ref "D7") (pin "A") (pinfunction "A_A") (pintype "passive"))
      (node (ref "D9") (pin "A") (pinfunction "A_A") (pintype "passive"))
      (node (ref "IC1") (pin "3") (pinfunction "GND_3") (pintype "passive"))
      (node (ref "IC2") (pin "3") (pinfunction "GND_3") (pintype "power_in"))
      (node (ref "IC2") (pin "7") (pinfunction "AD1_7") (pintype "power_in"))
      (node (ref "IC2") (pin "8") (pinfunction "AD0_8") (pintype "power_in"))
      (node (ref "K1") (pin "40") (pinfunction "40_40") (pintype "passive"))
      (node (ref "K2") (pin "39") (pinfunction "39_39") (pintype "passive"))
      (node (ref "K2") (pin "40") (pinfunction "40_40") (pintype "passive"))
      (node (ref "K5") (pin "3") (pinfunction "3_3") (pintype "passive"))
      (node (ref "OK1") (pin "11") (pinfunction "EMIT_11") (pintype "passive"))
      (node (ref "OK1") (pin "13") (pinfunction "EMIT_13") (pintype "passive"))
      (node (ref "OK1") (pin "15") (pinfunction "EMIT_15") (pintype "passive"))
      (node (ref "OK1") (pin "2") (pinfunction "C_2") (pintype "passive"))
      (node (ref "OK1") (pin "4") (pinfunction "C_4") (pintype "passive"))
      (node (ref "OK1") (pin "6") (pinfunction "C_6") (pintype "passive"))
      (node (ref "OK1") (pin "8") (pinfunction "C_8") (pintype "passive"))
      (node (ref "OK1") (pin "9") (pinfunction "EMIT_9") (pintype "passive"))
      (node (ref "OK2") (pin "11") (pinfunction "EMIT_11") (pintype "passive"))
      (node (ref "OK2") (pin "13") (pinfunction "EMIT_13") (pintype "passive"))
      (node (ref "OK2") (pin "15") (pinfunction "EMIT_15") (pintype "passive"))
      (node (ref "OK2") (pin "2") (pinfunction "C_2") (pintype "passive"))
      (node (ref "OK2") (pin "4") (pinfunction "C_4") (pintype "passive"))
      (node (ref "OK2") (pin "6") (pinfunction "C_6") (pintype "passive"))
      (node (ref "OK2") (pin "8") (pinfunction "C_8") (pintype "passive"))
      (node (ref "OK2") (pin "9") (pinfunction "EMIT_9") (pintype "passive"))
      (node (ref "Q1") (pin "2") (pinfunction "S_2") (pintype "passive"))
      (node (ref "Q10") (pin "2") (pinfunction "S_2") (pintype "passive"))
      (node (ref "Q2") (pin "2") (pinfunction "2_2") (pintype "passive"))
      (node (ref "Q2") (pin "4") (pinfunction "4_4") (pintype "passive"))
      (node (ref "Q4") (pin "2") (pinfunction "S_2") (pintype "passive"))
      (node (ref "Q5") (pin "2") (pinfunction "S_2") (pintype "passive"))
      (node (ref "Q6") (pin "2") (pinfunction "S_2") (pintype "passive"))
      (node (ref "Q7") (pin "2") (pinfunction "S_2") (pintype "passive"))
      (node (ref "Q8") (pin "2") (pinfunction "S_2") (pintype "passive"))
      (node (ref "Q9") (pin "2") (pinfunction "S_2") (pintype "passive"))
      (node (ref "QF1") (pin "2") (pinfunction "2_2") (pintype "passive"))
      (node (ref "R1") (pin "1") (pinfunction "1_1") (pintype "passive"))
      (node (ref "R12") (pin "1") (pinfunction "1_1") (pintype "passive"))
      (node (ref "R13") (pin "1") (pinfunction "1_1") (pintype "passive"))
      (node (ref "R15") (pin "1") (pinfunction "1_1") (pintype "passive"))
      (node (ref "R16") (pin "2") (pinfunction "2_2") (pintype "passive"))
      (node (ref "R24") (pin "1") (pinfunction "1_1") (pintype "passive"))
      (node (ref "R27") (pin "1") (pinfunction "1_1") (pintype "passive"))
      (node (ref "R35") (pin "1") (pinfunction "1_1") (pintype "passive"))
      (node (ref "R37") (pin "2") (pinfunction "2_2") (pintype "passive"))
      (node (ref "R38") (pin "1") (pinfunction "1_1") (pintype "passive"))
      (node (ref "R40") (pin "1") (pinfunction "1_1") (pintype "passive"))
      (node (ref "R42") (pin "1") (pinfunction "1_1") (pintype "passive"))
      (node (ref "R44") (pin "1") (pinfunction "1_1") (pintype "passive"))
      (node (ref "R46") (pin "1") (pinfunction "1_1") (pintype "passive"))
      (node (ref "R6") (pin "1") (pinfunction "1_1") (pintype "passive"))
      (node (ref "R61") (pin "1") (pinfunction "1_1") (pintype "passive"))
      (node (ref "R62") (pin "1") (pinfunction "1_1") (pintype "passive"))
      (node (ref "R63") (pin "1") (pinfunction "1_1") (pintype "passive"))
      (node (ref "R64") (pin "1") (pinfunction "1_1") (pintype "passive"))
      (node (ref "R65") (pin "1") (pinfunction "1_1") (pintype "passive"))
      (node (ref "R66") (pin "1") (pinfunction "1_1") (pintype "passive"))
      (node (ref "R67") (pin "1") (pinfunction "1_1") (pintype "passive"))
      (node (ref "U$1") (pin "GND") (pinfunction "GND_GND") (pintype "power_in"))
      (node (ref "U$2") (pin "23") (pinfunction "VSS_1(P23)_23") (pintype "bidirectional"))
      (node (ref "U$2") (pin "35") (pinfunction "VSS_2(P35)_35") (pintype "bidirectional"))
      (node (ref "U$2") (pin "47") (pinfunction "VSS_3(P47)_47") (pintype "bidirectional"))
      (node (ref "U$2") (pin "8") (pinfunction "VSSA(P8)_8") (pintype "bidirectional"))
      (node (ref "U$3") (pin "9") (pinfunction "VSS_9") (pintype "power_in"))
      (node (ref "U$4") (pin "2") (pinfunction "VSS_2") (pintype "passive"))
      (node (ref "U1") (pin "6") (pinfunction "GND_6") (pintype "passive"))
      (node (ref "U2") (pin "2") (pinfunction "GND_2") (pintype "passive"))
      (node (ref "U3") (pin "4") (pinfunction "GND_4") (pintype "passive"))
      (node (ref "U4") (pin "4") (pinfunction "GND_4") (pintype "passive"))
      (node (ref "U5") (pin "11") (pinfunction "VSSRX_11") (pintype "power_in"))
      (node (ref "U5") (pin "18") (pinfunction "VSSTX_18") (pintype "power_in"))
      (node (ref "U5") (pin "2") (pinfunction "VSS_2") (pintype "power_in"))
      (node (ref "U5") (pin "21") (pinfunction "VSSPLL_21") (pintype "power_in"))
      (node (ref "U5") (pin "22") (pinfunction "VSSOSC_22") (pintype "power_in"))
      (node (ref "X2") (pin "10") (pinfunction "KL_10") (pintype "passive"))
      (node (ref "X2") (pin "3") (pinfunction "KL_3") (pintype "passive"))
      (node (ref "X2") (pin "4") (pinfunction "KL_4") (pintype "passive"))
      (node (ref "X2") (pin "5") (pinfunction "KL_5") (pintype "passive"))
      (node (ref "X2") (pin "8") (pinfunction "KL_8") (pintype "passive"))
      (node (ref "X3") (pin "1") (pinfunction "KL_1") (pintype "passive"))
      (node (ref "X3") (pin "2") (pinfunction "KL_2") (pintype "passive"))
      (node (ref "X4") (pin "10") (pinfunction "KL_10") (pintype "passive"))
      (node (ref "X4") (pin "9") (pinfunction "KL_9") (pintype "passive"))
      (node (ref "X5") (pin "10") (pinfunction "KL_10") (pintype "passive"))
      (node (ref "X5") (pin "5") (pinfunction "KL_5") (pintype "passive"))
      (node (ref "X6") (pin "10") (pinfunction "KL_10") (pintype "passive"))
      (node (ref "X6") (pin "5") (pinfunction "KL_5") (pintype "passive"))
    )
    (net (code "98") (name "Net-(C1-Pad1)") (class "Default")
      (node (ref "C1") (pin "1") (pinfunction "1_1") (pintype "passive"))
      (node (ref "R3") (pin "2") (pinfunction "2_2") (pintype "passive"))
      (node (ref "R4") (pin "1") (pinfunction "1_1") (pintype "passive"))
    )
    (net (code "99") (name "Net-(C7-Pad1)") (class "Default")
      (node (ref "C7") (pin "1") (pinfunction "1_1") (pintype "passive"))
      (node (ref "R10") (pin "1") (pinfunction "1_1") (pintype "passive"))
      (node (ref "R9") (pin "2") (pinfunction "2_2") (pintype "passive"))
    )
    (net (code "100") (name "Net-(C9-Pad1)") (class "Default")
      (node (ref "C9") (pin "1") (pinfunction "1_1") (pintype "passive"))
      (node (ref "R14") (pin "2") (pinfunction "2_2") (pintype "passive"))
      (node (ref "R22") (pin "1") (pinfunction "1_1") (pintype "passive"))
    )
    (net (code "101") (name "Net-(C11-Pad1)") (class "Default")
      (node (ref "C11") (pin "1") (pinfunction "1_1") (pintype "passive"))
      (node (ref "R28") (pin "2") (pinfunction "2_2") (pintype "passive"))
      (node (ref "R29") (pin "1") (pinfunction "1_1") (pintype "passive"))
    )
    (net (code "102") (name "Net-(C32-Pad1)") (class "Default")
      (node (ref "C32") (pin "1") (pinfunction "1_1") (pintype "passive"))
      (node (ref "R20") (pin "1") (pinfunction "1_1") (pintype "passive"))
      (node (ref "R21") (pin "1") (pinfunction "1_1") (pintype "passive"))
    )
    (net (code "103") (name "Net-(D3-PadC)") (class "Default")
      (node (ref "D3") (pin "C") (pinfunction "C_C") (pintype "passive"))
      (node (ref "R8") (pin "1") (pinfunction "1_1") (pintype "passive"))
    )
    (net (code "104") (name "Net-(D6-PadC)") (class "Default")
      (node (ref "D6") (pin "C") (pinfunction "C_C") (pintype "passive"))
      (node (ref "R48") (pin "1") (pinfunction "1_1") (pintype "passive"))
    )
    (net (code "105") (name "Net-(D8-PadC)") (class "Default")
      (node (ref "D8") (pin "C") (pinfunction "C_C") (pintype "passive"))
      (node (ref "R50") (pin "1") (pinfunction "1_1") (pintype "passive"))
    )
    (net (code "106") (name "Net-(D10-PadC)") (class "Default")
      (node (ref "D10") (pin "C") (pinfunction "C_C") (pintype "passive"))
      (node (ref "R52") (pin "1") (pinfunction "1_1") (pintype "passive"))
    )
    (net (code "107") (name "Net-(D12-PadC)") (class "Default")
      (node (ref "D12") (pin "C") (pinfunction "C_C") (pintype "passive"))
      (node (ref "R54") (pin "1") (pinfunction "1_1") (pintype "passive"))
    )
    (net (code "108") (name "Net-(D14-PadC)") (class "Default")
      (node (ref "D14") (pin "C") (pinfunction "C_C") (pintype "passive"))
      (node (ref "R56") (pin "1") (pinfunction "1_1") (pintype "passive"))
    )
    (net (code "109") (name "Net-(D16-PadC)") (class "Default")
      (node (ref "D16") (pin "C") (pinfunction "C_C") (pintype "passive"))
      (node (ref "R58") (pin "1") (pinfunction "1_1") (pintype "passive"))
    )
    (net (code "110") (name "Net-(D18-PadC)") (class "Default")
      (node (ref "D18") (pin "C") (pinfunction "C_C") (pintype "passive"))
      (node (ref "R60") (pin "1") (pinfunction "1_1") (pintype "passive"))
    )
    (net (code "111") (name "Net-(IC2-PCTLZ)") (class "Default")
      (node (ref "IC2") (pin "6") (pinfunction "PCTLZ_6") (pintype "bidirectional"))
      (node (ref "Q12") (pin "1") (pinfunction "G_1") (pintype "passive"))
    )
    (net (code "112") (name "Net-(OK1A-A)") (class "Default")
      (node (ref "D3") (pin "A") (pinfunction "A_A") (pintype "passive"))
      (node (ref "D4") (pin "C") (pinfunction "C_C") (pintype "passive"))
      (node (ref "OK1") (pin "1") (pinfunction "A_1") (pintype "passive"))
    )
    (net (code "113") (name "Net-(OK1B-A)") (class "Default")
      (node (ref "D6") (pin "A") (pinfunction "A_A") (pintype "passive"))
      (node (ref "D7") (pin "C") (pinfunction "C_C") (pintype "passive"))
      (node (ref "OK1") (pin "3") (pinfunction "A_3") (pintype "passive"))
    )
    (net (code "114") (name "Net-(OK1C-A)") (class "Default")
      (node (ref "D8") (pin "A") (pinfunction "A_A") (pintype "passive"))
      (node (ref "D9") (pin "C") (pinfunction "C_C") (pintype "passive"))
      (node (ref "OK1") (pin "5") (pinfunction "A_5") (pintype "passive"))
    )
    (net (code "115") (name "Net-(OK1D-A)") (class "Default")
      (node (ref "D10") (pin "A") (pinfunction "A_A") (pintype "passive"))
      (node (ref "D11") (pin "C") (pinfunction "C_C") (pintype "passive"))
      (node (ref "OK1") (pin "7") (pinfunction "A_7") (pintype "passive"))
    )
    (net (code "116") (name "Net-(OK2A-A)") (class "Default")
      (node (ref "D12") (pin "A") (pinfunction "A_A") (pintype "passive"))
      (node (ref "D13") (pin "C") (pinfunction "C_C") (pintype "passive"))
      (node (ref "OK2") (pin "1") (pinfunction "A_1") (pintype "passive"))
    )
    (net (code "117") (name "Net-(OK2B-A)") (class "Default")
      (node (ref "D14") (pin "A") (pinfunction "A_A") (pintype "passive"))
      (node (ref "D15") (pin "C") (pinfunction "C_C") (pintype "passive"))
      (node (ref "OK2") (pin "3") (pinfunction "A_3") (pintype "passive"))
    )
    (net (code "118") (name "Net-(OK2C-A)") (class "Default")
      (node (ref "D16") (pin "A") (pinfunction "A_A") (pintype "passive"))
      (node (ref "D17") (pin "C") (pinfunction "C_C") (pintype "passive"))
      (node (ref "OK2") (pin "5") (pinfunction "A_5") (pintype "passive"))
    )
    (net (code "119") (name "Net-(OK2D-A)") (class "Default")
      (node (ref "D18") (pin "A") (pinfunction "A_A") (pintype "passive"))
      (node (ref "D19") (pin "C") (pinfunction "C_C") (pintype "passive"))
      (node (ref "OK2") (pin "7") (pinfunction "A_7") (pintype "passive"))
    )
    (net (code "120") (name "Net-(Q1-D)") (class "Default")
      (node (ref "D1") (pin "A") (pinfunction "A_A") (pintype "passive"))
      (node (ref "Q1") (pin "3") (pinfunction "D_3") (pintype "passive"))
      (node (ref "S1") (pin "A2") (pinfunction "A2_A2") (pintype "bidirectional"))
    )
    (net (code "121") (name "Net-(Q4-D)") (class "Default")
      (node (ref "D20") (pin "A") (pinfunction "A_A") (pintype "passive"))
      (node (ref "Q4") (pin "3") (pinfunction "D_3") (pintype "passive"))
      (node (ref "S2") (pin "A2") (pinfunction "A2_A2") (pintype "bidirectional"))
    )
    (net (code "122") (name "Net-(Q5-D)") (class "Default")
      (node (ref "D21") (pin "A") (pinfunction "A_A") (pintype "passive"))
      (node (ref "Q5") (pin "3") (pinfunction "D_3") (pintype "passive"))
      (node (ref "S3") (pin "A2") (pinfunction "A2_A2") (pintype "bidirectional"))
    )
    (net (code "123") (name "Net-(Q6-D)") (class "Default")
      (node (ref "D22") (pin "A") (pinfunction "A_A") (pintype "passive"))
      (node (ref "Q6") (pin "3") (pinfunction "D_3") (pintype "passive"))
      (node (ref "S4") (pin "A2") (pinfunction "A2_A2") (pintype "bidirectional"))
    )
    (net (code "124") (name "Net-(Q7-D)") (class "Default")
      (node (ref "D23") (pin "A") (pinfunction "A_A") (pintype "passive"))
      (node (ref "Q7") (pin "3") (pinfunction "D_3") (pintype "passive"))
      (node (ref "S5") (pin "A2") (pinfunction "A2_A2") (pintype "bidirectional"))
    )
    (net (code "125") (name "Net-(Q8-D)") (class "Default")
      (node (ref "D24") (pin "A") (pinfunction "A_A") (pintype "passive"))
      (node (ref "Q8") (pin "3") (pinfunction "D_3") (pintype "passive"))
      (node (ref "S6") (pin "A2") (pinfunction "A2_A2") (pintype "bidirectional"))
    )
    (net (code "126") (name "Net-(Q9-D)") (class "Default")
      (node (ref "D25") (pin "A") (pinfunction "A_A") (pintype "passive"))
      (node (ref "Q9") (pin "3") (pinfunction "D_3") (pintype "passive"))
      (node (ref "S7") (pin "A2") (pinfunction "A2_A2") (pintype "bidirectional"))
    )
    (net (code "127") (name "Net-(Q10-D)") (class "Default")
      (node (ref "D26") (pin "A") (pinfunction "A_A") (pintype "passive"))
      (node (ref "Q10") (pin "3") (pinfunction "D_3") (pintype "passive"))
      (node (ref "S8") (pin "A2") (pinfunction "A2_A2") (pintype "bidirectional"))
    )
    (net (code "128") (name "Net-(Q12-S)") (class "Default")
      (node (ref "Q12") (pin "2") (pinfunction "S_2") (pintype "passive"))
      (node (ref "R31") (pin "1") (pinfunction "1_1") (pintype "passive"))
    )
    (net (code "129") (name "Net-(U$2-VBATT(P1))") (class "Default")
      (node (ref "U$1") (pin "V+") (pinfunction "V+_V+") (pintype "power_in"))
      (node (ref "U$2") (pin "1") (pinfunction "VBATT(P1)_1") (pintype "bidirectional"))
    )
    (net (code "130") (name "Net-(U$3-RXCAN)") (class "Default")
      (node (ref "R36") (pin "1") (pinfunction "1_1") (pintype "passive"))
      (node (ref "R37") (pin "1") (pinfunction "1_1") (pintype "passive"))
      (node (ref "U$3") (pin "2") (pinfunction "RXCAN_2") (pintype "input"))
    )
    (net (code "131") (name "Net-(U$3-TXCAN)") (class "Default")
      (node (ref "U$3") (pin "1") (pinfunction "TXCAN_1") (pintype "output"))
      (node (ref "U$4") (pin "1") (pinfunction "TXD_1") (pintype "input"))
    )
    (net (code "132") (name "Net-(U$4-RS)") (class "Default")
      (node (ref "R38") (pin "2") (pinfunction "2_2") (pintype "passive"))
      (node (ref "U$4") (pin "8") (pinfunction "RS_8") (pintype "input"))
    )
    (net (code "133") (name "Net-(U1-CB)") (class "Default")
      (node (ref "C3") (pin "2") (pinfunction "2_2") (pintype "passive"))
      (node (ref "U1") (pin "1") (pinfunction "CB_1") (pintype "passive"))
    )
    (net (code "134") (name "Net-(U1-VSW)") (class "Default")
      (node (ref "C3") (pin "1") (pinfunction "1_1") (pintype "passive"))
      (node (ref "D2") (pin "C") (pinfunction "C_C") (pintype "passive"))
      (node (ref "L1") (pin "2") (pinfunction "2_2") (pintype "passive"))
      (node (ref "U1") (pin "8") (pinfunction "VSW_8") (pintype "passive"))
    )
    (net (code "135") (name "Net-(U3-1IN+)") (class "Default")
      (node (ref "C2") (pin "1") (pinfunction "1_1") (pintype "passive"))
      (node (ref "R4") (pin "2") (pinfunction "2_2") (pintype "passive"))
      (node (ref "U3") (pin "3") (pinfunction "1IN+_3") (pintype "input"))
    )
    (net (code "136") (name "Net-(U3-1IN-)") (class "Default")
      (node (ref "R5") (pin "1") (pinfunction "1_1") (pintype "passive"))
      (node (ref "R6") (pin "2") (pinfunction "2_2") (pintype "passive"))
      (node (ref "U3") (pin "2") (pinfunction "1IN-_2") (pintype "input"))
    )
    (net (code "137") (name "Net-(U3-2IN+)") (class "Default")
      (node (ref "C8") (pin "1") (pinfunction "1_1") (pintype "passive"))
      (node (ref "R10") (pin "2") (pinfunction "2_2") (pintype "passive"))
      (node (ref "U3") (pin "5") (pinfunction "2IN+_5") (pintype "input"))
    )
    (net (code "138") (name "Net-(U3-2IN-)") (class "Default")
      (node (ref "R11") (pin "1") (pinfunction "1_1") (pintype "passive"))
      (node (ref "R13") (pin "2") (pinfunction "2_2") (pintype "passive"))
      (node (ref "U3") (pin "6") (pinfunction "2IN-_6") (pintype "input"))
    )
    (net (code "139") (name "Net-(U4-1IN+)") (class "Default")
      (node (ref "C10") (pin "1") (pinfunction "1_1") (pintype "passive"))
      (node (ref "R22") (pin "2") (pinfunction "2_2") (pintype "passive"))
      (node (ref "U4") (pin "3") (pinfunction "1IN+_3") (pintype "input"))
    )
    (net (code "140") (name "Net-(U4-1IN-)") (class "Default")
      (node (ref "R23") (pin "1") (pinfunction "1_1") (pintype "passive"))
      (node (ref "R27") (pin "2") (pinfunction "2_2") (pintype "passive"))
      (node (ref "U4") (pin "2") (pinfunction "1IN-_2") (pintype "input"))
    )
    (net (code "141") (name "Net-(U4-2IN+)") (class "Default")
      (node (ref "C12") (pin "1") (pinfunction "1_1") (pintype "passive"))
      (node (ref "R29") (pin "2") (pinfunction "2_2") (pintype "passive"))
      (node (ref "U4") (pin "5") (pinfunction "2IN+_5") (pintype "input"))
    )
    (net (code "142") (name "Net-(U4-2IN-)") (class "Default")
      (node (ref "R30") (pin "1") (pinfunction "1_1") (pintype "passive"))
      (node (ref "R35") (pin "2") (pinfunction "2_2") (pintype "passive"))
      (node (ref "U4") (pin "6") (pinfunction "2IN-_6") (pintype "input"))
    )
    (net (code "143") (name "Net-(U5-RBIAS)") (class "Default")
      (node (ref "R16") (pin "1") (pinfunction "1_1") (pintype "passive"))
      (node (ref "U5") (pin "14") (pinfunction "RBIAS_14") (pintype "passive"))
    )
    (net (code "144") (name "Net-(U5-VCAP)") (class "Default")
      (node (ref "C23") (pin "1") (pinfunction "1_1") (pintype "passive"))
      (node (ref "U5") (pin "1") (pinfunction "VCAP_1") (pintype "power_in"))
    )
    (net (code "145") (name "Net-(X1-C-L)") (class "Default")
      (node (ref "R15") (pin "2") (pinfunction "2_2") (pintype "passive"))
      (node (ref "X1") (pin "11") (pinfunction "C-L_11") (pintype "passive"))
    )
    (net (code "146") (name "Net-(X1-C-R)") (class "Default")
      (node (ref "R12") (pin "2") (pinfunction "2_2") (pintype "passive"))
      (node (ref "X1") (pin "10") (pinfunction "C-R_10") (pintype "passive"))
    )
    (net (code "147") (name "VCC") (class "Default")
      (node (ref "C13") (pin "1") (pinfunction "1_1") (pintype "passive"))
      (node (ref "C14") (pin "+") (pinfunction "+_+") (pintype "passive"))
      (node (ref "C37") (pin "1") (pinfunction "1_1") (pintype "passive"))
      (node (ref "D1") (pin "C") (pinfunction "C_C") (pintype "passive"))
      (node (ref "D20") (pin "C") (pinfunction "C_C") (pintype "passive"))
      (node (ref "D21") (pin "C") (pinfunction "C_C") (pintype "passive"))
      (node (ref "D22") (pin "C") (pinfunction "C_C") (pintype "passive"))
      (node (ref "D23") (pin "C") (pinfunction "C_C") (pintype "passive"))
      (node (ref "D24") (pin "C") (pinfunction "C_C") (pintype "passive"))
      (node (ref "D25") (pin "C") (pinfunction "C_C") (pintype "passive"))
      (node (ref "D26") (pin "C") (pinfunction "C_C") (pintype "passive"))
      (node (ref "D5") (pin "C") (pinfunction "C_C") (pintype "passive"))
      (node (ref "F1") (pin "2") (pinfunction "2_2") (pintype "passive"))
      (node (ref "IC1") (pin "1") (pinfunction "VI_1") (pintype "input"))
      (node (ref "S1") (pin "A1") (pinfunction "A1_A1") (pintype "bidirectional"))
      (node (ref "S2") (pin "A1") (pinfunction "A1_A1") (pintype "bidirectional"))
      (node (ref "S3") (pin "A1") (pinfunction "A1_A1") (pintype "bidirectional"))
      (node (ref "S4") (pin "A1") (pinfunction "A1_A1") (pintype "bidirectional"))
      (node (ref "S5") (pin "A1") (pinfunction "A1_A1") (pintype "bidirectional"))
      (node (ref "S6") (pin "A1") (pinfunction "A1_A1") (pintype "bidirectional"))
      (node (ref "S7") (pin "A1") (pinfunction "A1_A1") (pintype "bidirectional"))
      (node (ref "S8") (pin "A1") (pinfunction "A1_A1") (pintype "bidirectional"))
      (node (ref "U1") (pin "7") (pinfunction "VIN_7") (pintype "power_in"))
      (node (ref "U2") (pin "1") (pinfunction "IN_1") (pintype "input"))
      (node (ref "U2") (pin "3") (pinfunction "EN_3") (pintype "input"))
    )
    (net (code "148") (name "unconnected-(K1-Pad9)") (class "Default")
      (node (ref "K1") (pin "9") (pinfunction "9_9") (pintype "passive"))
    )
    (net (code "149") (name "unconnected-(K1-Pad10)") (class "Default")
      (node (ref "K1") (pin "10") (pinfunction "10_10") (pintype "passive"))
    )
    (net (code "150") (name "unconnected-(K1-Pad15)") (class "Default")
      (node (ref "K1") (pin "15") (pinfunction "15_15") (pintype "passive"))
    )
    (net (code "151") (name "unconnected-(K1-Pad16)") (class "Default")
      (node (ref "K1") (pin "16") (pinfunction "16_16") (pintype "passive"))
    )
    (net (code "152") (name "unconnected-(K1-Pad17)") (class "Default")
      (node (ref "K1") (pin "17") (pinfunction "17_17") (pintype "passive"))
    )
    (net (code "153") (name "unconnected-(K1-Pad18)") (class "Default")
      (node (ref "K1") (pin "18") (pinfunction "18_18") (pintype "passive"))
    )
    (net (code "154") (name "unconnected-(K1-Pad19)") (class "Default")
      (node (ref "K1") (pin "19") (pinfunction "19_19") (pintype "passive"))
    )
    (net (code "155") (name "unconnected-(K1-Pad20)") (class "Default")
      (node (ref "K1") (pin "20") (pinfunction "20_20") (pintype "passive"))
    )
    (net (code "156") (name "unconnected-(K1-Pad21)") (class "Default")
      (node (ref "K1") (pin "21") (pinfunction "21_21") (pintype "passive"))
    )
    (net (code "157") (name "unconnected-(K1-Pad22)") (class "Default")
      (node (ref "K1") (pin "22") (pinfunction "22_22") (pintype "passive"))
    )
    (net (code "158") (name "unconnected-(K1-Pad23)") (class "Default")
      (node (ref "K1") (pin "23") (pinfunction "23_23") (pintype "passive"))
    )
    (net (code "159") (name "unconnected-(K1-Pad24)") (class "Default")
      (node (ref "K1") (pin "24") (pinfunction "24_24") (pintype "passive"))
    )
    (net (code "160") (name "unconnected-(K1-Pad25)") (class "Default")
      (node (ref "K1") (pin "25") (pinfunction "25_25") (pintype "passive"))
    )
    (net (code "161") (name "unconnected-(K1-Pad26)") (class "Default")
      (node (ref "K1") (pin "26") (pinfunction "26_26") (pintype "passive"))
    )
    (net (code "162") (name "unconnected-(K1-Pad27)") (class "Default")
      (node (ref "K1") (pin "27") (pinfunction "27_27") (pintype "passive"))
    )
    (net (code "163") (name "unconnected-(K1-Pad28)") (class "Default")
      (node (ref "K1") (pin "28") (pinfunction "28_28") (pintype "passive"))
    )
    (net (code "164") (name "unconnected-(K1-Pad29)") (class "Default")
      (node (ref "K1") (pin "29") (pinfunction "29_29") (pintype "passive"))
    )
    (net (code "165") (name "unconnected-(K1-Pad30)") (class "Default")
      (node (ref "K1") (pin "30") (pinfunction "30_30") (pintype "passive"))
    )
    (net (code "166") (name "unconnected-(K1-Pad31)") (class "Default")
      (node (ref "K1") (pin "31") (pinfunction "31_31") (pintype "passive"))
    )
    (net (code "167") (name "unconnected-(K1-Pad32)") (class "Default")
      (node (ref "K1") (pin "32") (pinfunction "32_32") (pintype "passive"))
    )
    (net (code "168") (name "unconnected-(K1-Pad33)") (class "Default")
      (node (ref "K1") (pin "33") (pinfunction "33_33") (pintype "passive"))
    )
    (net (code "169") (name "unconnected-(K1-Pad34)") (class "Default")
      (node (ref "K1") (pin "34") (pinfunction "34_34") (pintype "passive"))
    )
    (net (code "170") (name "unconnected-(K1-Pad35)") (class "Default")
      (node (ref "K1") (pin "35") (pinfunction "35_35") (pintype "passive"))
    )
    (net (code "171") (name "unconnected-(K1-Pad36)") (class "Default")
      (node (ref "K1") (pin "36") (pinfunction "36_36") (pintype "passive"))
    )
    (net (code "172") (name "unconnected-(K1-Pad37)") (class "Default")
      (node (ref "K1") (pin "37") (pinfunction "37_37") (pintype "passive"))
    )
    (net (code "173") (name "unconnected-(K1-Pad38)") (class "Default")
      (node (ref "K1") (pin "38") (pinfunction "38_38") (pintype "passive"))
    )
    (net (code "174") (name "unconnected-(K1-Pad39)") (class "Default")
      (node (ref "K1") (pin "39") (pinfunction "39_39") (pintype "passive"))
    )
    (net (code "175") (name "unconnected-(K2-Pad1)") (class "Default")
      (node (ref "K2") (pin "1") (pinfunction "1_1") (pintype "passive"))
    )
    (net (code "176") (name "unconnected-(K2-Pad2)") (class "Default")
      (node (ref "K2") (pin "2") (pinfunction "2_2") (pintype "passive"))
    )
    (net (code "177") (name "unconnected-(K2-Pad3)") (class "Default")
      (node (ref "K2") (pin "3") (pinfunction "3_3") (pintype "passive"))
    )
    (net (code "178") (name "unconnected-(K2-Pad4)") (class "Default")
      (node (ref "K2") (pin "4") (pinfunction "4_4") (pintype "passive"))
    )
    (net (code "179") (name "unconnected-(K2-Pad5)") (class "Default")
      (node (ref "K2") (pin "5") (pinfunction "5_5") (pintype "passive"))
    )
    (net (code "180") (name "unconnected-(K2-Pad6)") (class "Default")
      (node (ref "K2") (pin "6") (pinfunction "6_6") (pintype "passive"))
    )
    (net (code "181") (name "unconnected-(K2-Pad7)") (class "Default")
      (node (ref "K2") (pin "7") (pinfunction "7_7") (pintype "passive"))
    )
    (net (code "182") (name "unconnected-(K2-Pad8)") (class "Default")
      (node (ref "K2") (pin "8") (pinfunction "8_8") (pintype "passive"))
    )
    (net (code "183") (name "unconnected-(K2-Pad9)") (class "Default")
      (node (ref "K2") (pin "9") (pinfunction "9_9") (pintype "passive"))
    )
    (net (code "184") (name "unconnected-(K2-Pad10)") (class "Default")
      (node (ref "K2") (pin "10") (pinfunction "10_10") (pintype "passive"))
    )
    (net (code "185") (name "unconnected-(K2-Pad11)") (class "Default")
      (node (ref "K2") (pin "11") (pinfunction "11_11") (pintype "passive"))
    )
    (net (code "186") (name "unconnected-(K2-Pad12)") (class "Default")
      (node (ref "K2") (pin "12") (pinfunction "12_12") (pintype "passive"))
    )
    (net (code "187") (name "unconnected-(K2-Pad13)") (class "Default")
      (node (ref "K2") (pin "13") (pinfunction "13_13") (pintype "passive"))
    )
    (net (code "188") (name "unconnected-(K2-Pad14)") (class "Default")
      (node (ref "K2") (pin "14") (pinfunction "14_14") (pintype "passive"))
    )
    (net (code "189") (name "unconnected-(K2-Pad15)") (class "Default")
      (node (ref "K2") (pin "15") (pinfunction "15_15") (pintype "passive"))
    )
    (net (code "190") (name "unconnected-(K2-Pad16)") (class "Default")
      (node (ref "K2") (pin "16") (pinfunction "16_16") (pintype "passive"))
    )
    (net (code "191") (name "unconnected-(K2-Pad17)") (class "Default")
      (node (ref "K2") (pin "17") (pinfunction "17_17") (pintype "passive"))
    )
    (net (code "192") (name "unconnected-(K2-Pad18)") (class "Default")
      (node (ref "K2") (pin "18") (pinfunction "18_18") (pintype "passive"))
    )
    (net (code "193") (name "unconnected-(K2-Pad19)") (class "Default")
      (node (ref "K2") (pin "19") (pinfunction "19_19") (pintype "passive"))
    )
    (net (code "194") (name "unconnected-(K2-Pad20)") (class "Default")
      (node (ref "K2") (pin "20") (pinfunction "20_20") (pintype "passive"))
    )
    (net (code "195") (name "unconnected-(K2-Pad21)") (class "Default")
      (node (ref "K2") (pin "21") (pinfunction "21_21") (pintype "passive"))
    )
    (net (code "196") (name "unconnected-(K2-Pad22)") (class "Default")
      (node (ref "K2") (pin "22") (pinfunction "22_22") (pintype "passive"))
    )
    (net (code "197") (name "unconnected-(K2-Pad23)") (class "Default")
      (node (ref "K2") (pin "23") (pinfunction "23_23") (pintype "passive"))
    )
    (net (code "198") (name "unconnected-(K2-Pad24)") (class "Default")
      (node (ref "K2") (pin "24") (pinfunction "24_24") (pintype "passive"))
    )
    (net (code "199") (name "unconnected-(K2-Pad25)") (class "Default")
      (node (ref "K2") (pin "25") (pinfunction "25_25") (pintype "passive"))
    )
    (net (code "200") (name "unconnected-(K2-Pad26)") (class "Default")
      (node (ref "K2") (pin "26") (pinfunction "26_26") (pintype "passive"))
    )
    (net (code "201") (name "unconnected-(K2-Pad27)") (class "Default")
      (node (ref "K2") (pin "27") (pinfunction "27_27") (pintype "passive"))
    )
    (net (code "202") (name "unconnected-(K2-Pad28)") (class "Default")
      (node (ref "K2") (pin "28") (pinfunction "28_28") (pintype "passive"))
    )
    (net (code "203") (name "unconnected-(K2-Pad29)") (class "Default")
      (node (ref "K2") (pin "29") (pinfunction "29_29") (pintype "passive"))
    )
    (net (code "204") (name "unconnected-(K2-Pad30)") (class "Default")
      (node (ref "K2") (pin "30") (pinfunction "30_30") (pintype "passive"))
    )
    (net (code "205") (name "unconnected-(K2-Pad31)") (class "Default")
      (node (ref "K2") (pin "31") (pinfunction "31_31") (pintype "passive"))
    )
    (net (code "206") (name "unconnected-(K2-Pad32)") (class "Default")
      (node (ref "K2") (pin "32") (pinfunction "32_32") (pintype "passive"))
    )
    (net (code "207") (name "unconnected-(K2-Pad33)") (class "Default")
      (node (ref "K2") (pin "33") (pinfunction "33_33") (pintype "passive"))
    )
    (net (code "208") (name "unconnected-(K2-Pad34)") (class "Default")
      (node (ref "K2") (pin "34") (pinfunction "34_34") (pintype "passive"))
    )
    (net (code "209") (name "unconnected-(K2-Pad35)") (class "Default")
      (node (ref "K2") (pin "35") (pinfunction "35_35") (pintype "passive"))
    )
    (net (code "210") (name "unconnected-(K2-Pad36)") (class "Default")
      (node (ref "K2") (pin "36") (pinfunction "36_36") (pintype "passive"))
    )
    (net (code "211") (name "unconnected-(K2-Pad37)") (class "Default")
      (node (ref "K2") (pin "37") (pinfunction "37_37") (pintype "passive"))
    )
    (net (code "212") (name "unconnected-(K2-Pad38)") (class "Default")
      (node (ref "K2") (pin "38") (pinfunction "38_38") (pintype "passive"))
    )
    (net (code "213") (name "unconnected-(K4-Pad5)") (class "Default")
      (node (ref "K4") (pin "5") (pinfunction "5_5") (pintype "passive"))
    )
    (net (code "214") (name "unconnected-(K4-Pad6)") (class "Default")
      (node (ref "K4") (pin "6") (pinfunction "6_6") (pintype "passive"))
    )
    (net (code "215") (name "unconnected-(K4-Pad7)") (class "Default")
      (node (ref "K4") (pin "7") (pinfunction "7_7") (pintype "passive"))
    )
    (net (code "216") (name "unconnected-(K4-Pad8)") (class "Default")
      (node (ref "K4") (pin "8") (pinfunction "8_8") (pintype "passive"))
    )
    (net (code "217") (name "unconnected-(K4-Pad9)") (class "Default")
      (node (ref "K4") (pin "9") (pinfunction "9_9") (pintype "passive"))
    )
    (net (code "218") (name "unconnected-(K4-Pad10)") (class "Default")
      (node (ref "K4") (pin "10") (pinfunction "10_10") (pintype "passive"))
    )
    (net (code "219") (name "unconnected-(K5-Pad6)") (class "Default")
      (node (ref "K5") (pin "6") (pinfunction "6_6") (pintype "passive"))
    )
    (net (code "220") (name "unconnected-(U$2-PA12{slash}USB_DP{slash}CAN_TX-Pad33)") (class "Default")
      (node (ref "U$2") (pin "33") (pinfunction "PA12/USB_DP/CAN_TX_33") (pintype "bidirectional"))
    )
    (net (code "221") (name "unconnected-(U$2-PA15{slash}USART2_RX-Pad38)") (class "Default")
      (node (ref "U$2") (pin "38") (pinfunction "PA15/USART2_RX_38") (pintype "bidirectional"))
    )
    (net (code "222") (name "unconnected-(U$2-PC13{slash}WKUP2{slash}RTC_TAMP1{slash}RTC_TS{slash}RTC_OUT-Pad2)") (class "Default")
      (node (ref "U$2") (pin "2") (pinfunction "PC13/WKUP2/RTC_TAMP1/RTC_TS/RTC_OUT_2") (pintype "bidirectional"))
    )
    (net (code "223") (name "unconnected-(U$2-PF0{slash}OSC_IN-Pad5)") (class "Default")
      (node (ref "U$2") (pin "5") (pinfunction "PF0/OSC_IN_5") (pintype "bidirectional"))
    )
    (net (code "224") (name "unconnected-(U$2-PF1{slash}OSC_OUT-Pad6)") (class "Default")
      (node (ref "U$2") (pin "6") (pinfunction "PF1/OSC_OUT_6") (pintype "bidirectional"))
    )
    (net (code "225") (name "unconnected-(U$3-CLKOUT{slash}SOF-Pad3)") (class "Default")
      (node (ref "U$3") (pin "3") (pinfunction "CLKOUT/SOF_3") (pintype "output"))
    )
    (net (code "226") (name "unconnected-(U$3-~{RX0BF}-Pad11)") (class "Default")
      (node (ref "U$3") (pin "11") (pinfunction "~{RX0BF}_11") (pintype "output"))
    )
    (net (code "227") (name "unconnected-(U$3-~{RX1BF}-Pad10)") (class "Default")
      (node (ref "U$3") (pin "10") (pinfunction "~{RX1BF}_10") (pintype "output"))
    )
    (net (code "228") (name "unconnected-(U$3-~{TX0RTS}-Pad4)") (class "Default")
      (node (ref "U$3") (pin "4") (pinfunction "~{TX0RTS}_4") (pintype "input"))
    )
    (net (code "229") (name "unconnected-(U$3-~{TX1RTS}-Pad5)") (class "Default")
      (node (ref "U$3") (pin "5") (pinfunction "~{TX1RTS}_5") (pintype "input"))
    )
    (net (code "230") (name "unconnected-(U$3-~{TX2RTS}-Pad6)") (class "Default")
      (node (ref "U$3") (pin "6") (pinfunction "~{TX2RTS}_6") (pintype "input"))
    )
    (net (code "231") (name "unconnected-(U$4-VREF-Pad5)") (class "Default")
      (node (ref "U$4") (pin "5") (pinfunction "VREF_5") (pintype "output"))
    )
    (net (code "232") (name "unconnected-(U1-ON{slash}~{OFF}-Pad5)") (class "Default")
      (node (ref "U1") (pin "5") (pinfunction "ON/~{OFF}_5") (pintype "passive"))
    )
    (net (code "233") (name "unconnected-(U1-SS-Pad2)") (class "Default")
      (node (ref "U1") (pin "2") (pinfunction "SS_2") (pintype "passive"))
    )
    (net (code "234") (name "unconnected-(U1-SYNC-Pad3)") (class "Default")
      (node (ref "U1") (pin "3") (pinfunction "SYNC_3") (pintype "passive"))
    )
    (net (code "235") (name "unconnected-(U2-NC-Pad4)") (class "Default")
      (node (ref "U2") (pin "4") (pinfunction "NC_4") (pintype "no_connect"))
    )
    (net (code "236") (name "unconnected-(U5-CLKOUT-Pad3)") (class "Default")
      (node (ref "U5") (pin "3") (pinfunction "CLKOUT_3") (pintype "passive"))
    )
    (net (code "237") (name "unconnected-(U5-NC-Pad5)") (class "Default")
      (node (ref "U5") (pin "5") (pinfunction "NC_5") (pintype "no_connect"))
    )
    (net (code "238") (name "unconnected-(X1-CR-Pad6)") (class "Default")
      (node (ref "X1") (pin "6") (pinfunction "CR_6") (pintype "input"))
    )
    (net (code "239") (name "unconnected-(X1-NC{slash}4-Pad4)") (class "Default")
      (node (ref "X1") (pin "4") (pinfunction "NC/4_4") (pintype "input"))
    )
    (net (code "240") (name "unconnected-(X1-NC{slash}5-Pad5)") (class "Default")
      (node (ref "X1") (pin "5") (pinfunction "NC/5_5") (pintype "input"))
    )
  )
)
